# RF-BPF.net
KiCad netlist of a schematic drawn in Altium Designer
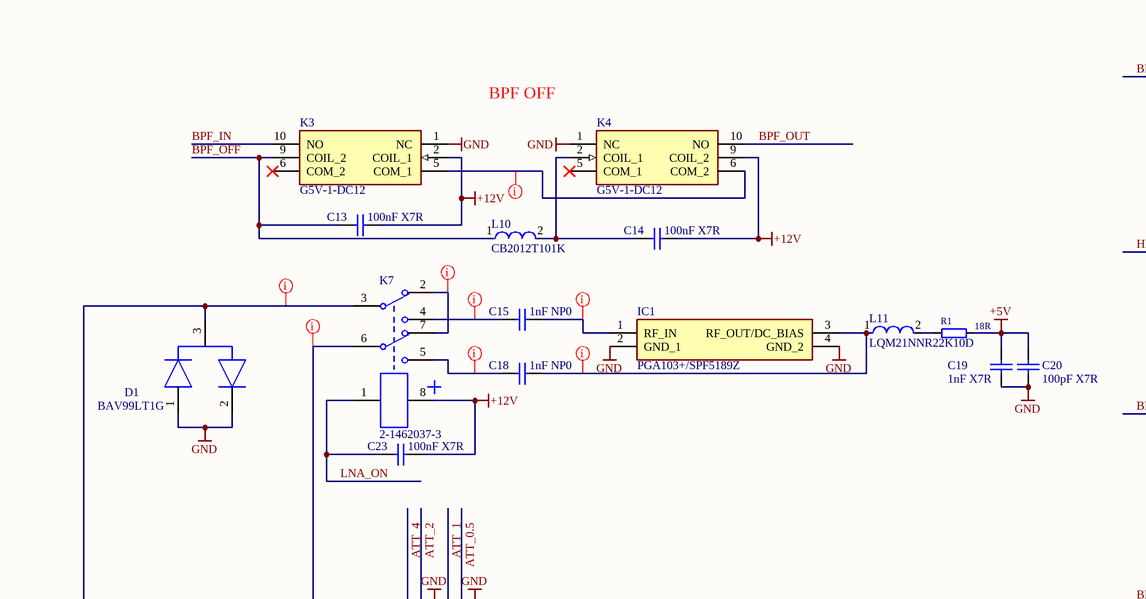
[diagram p0: RF-BPF.SchDoc, top left]
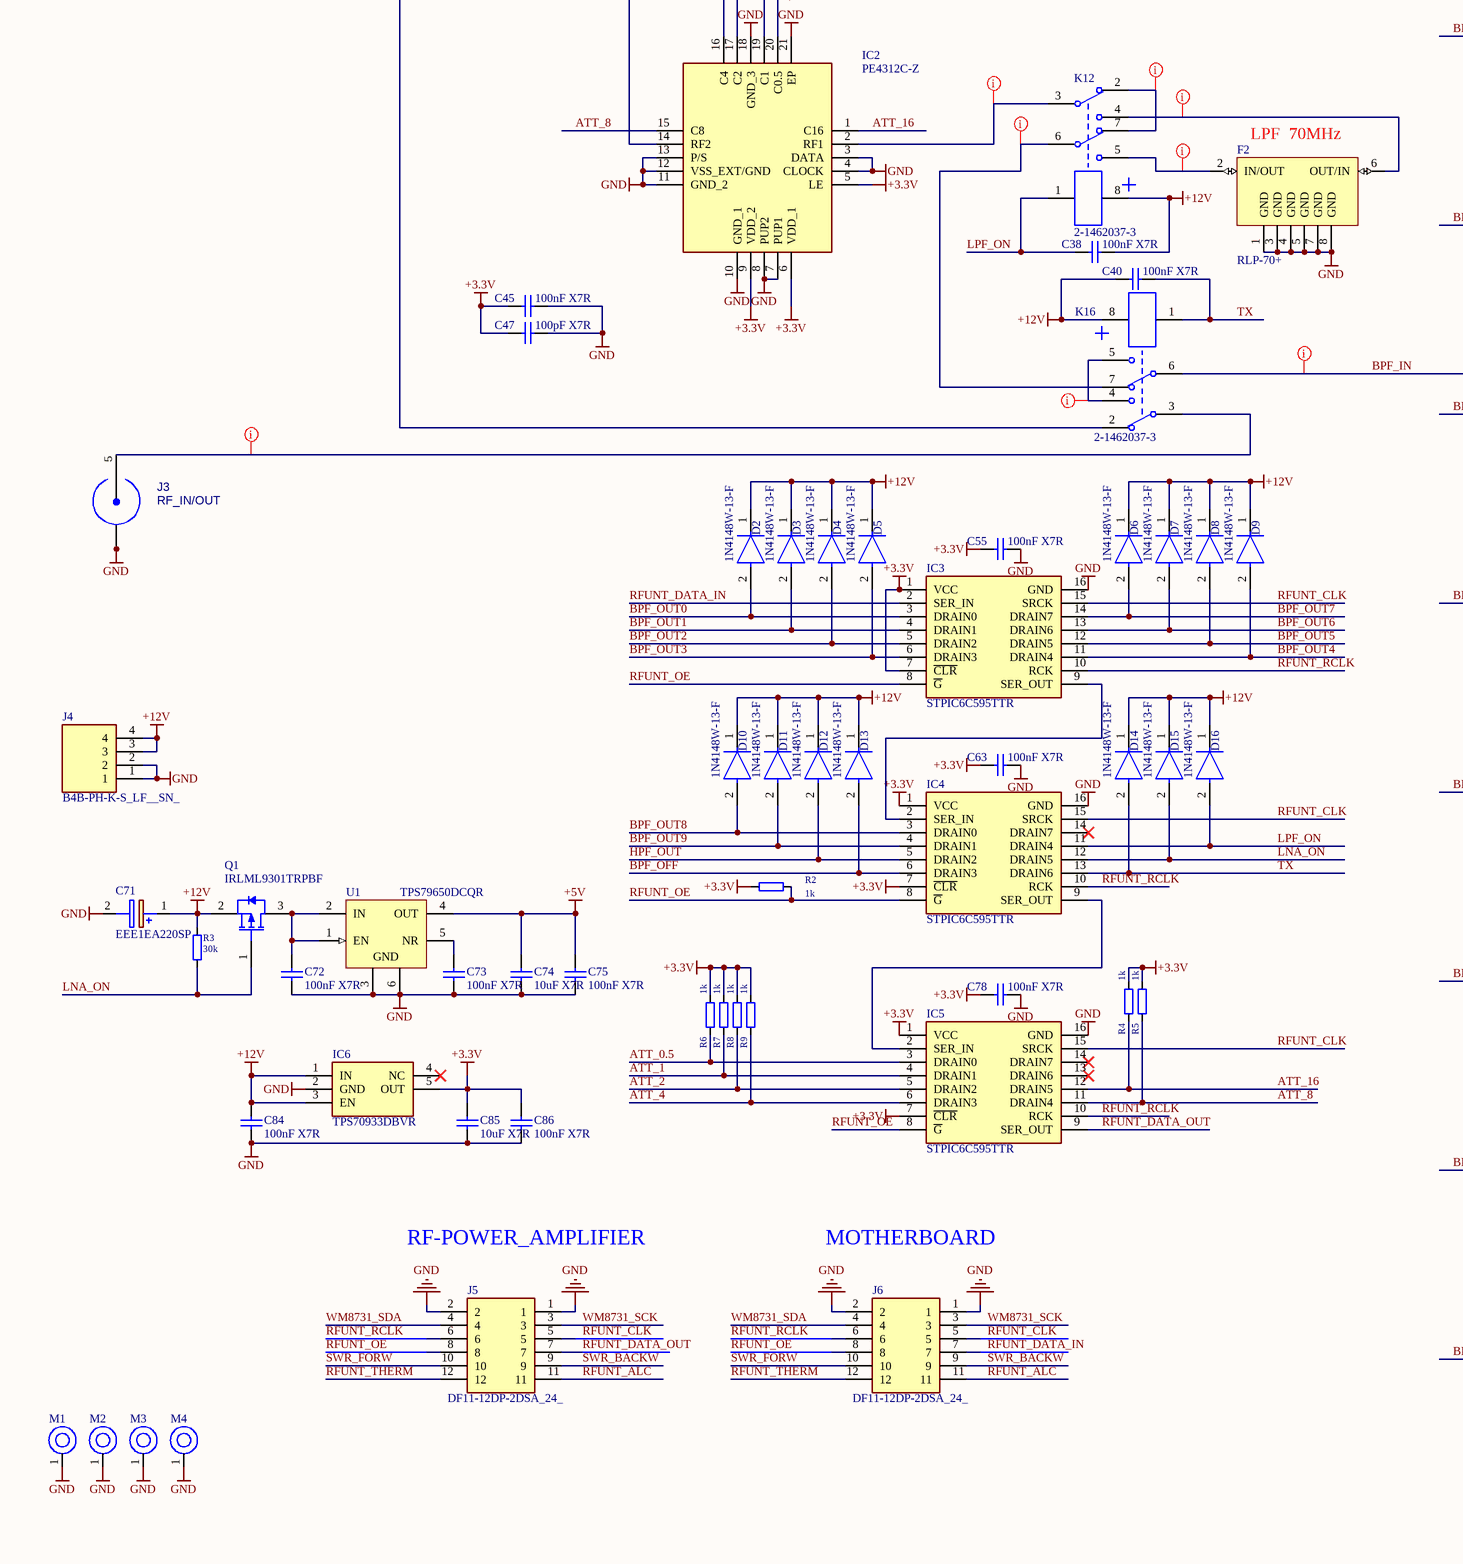
[diagram p1: RF-BPF.SchDoc, bottom left]
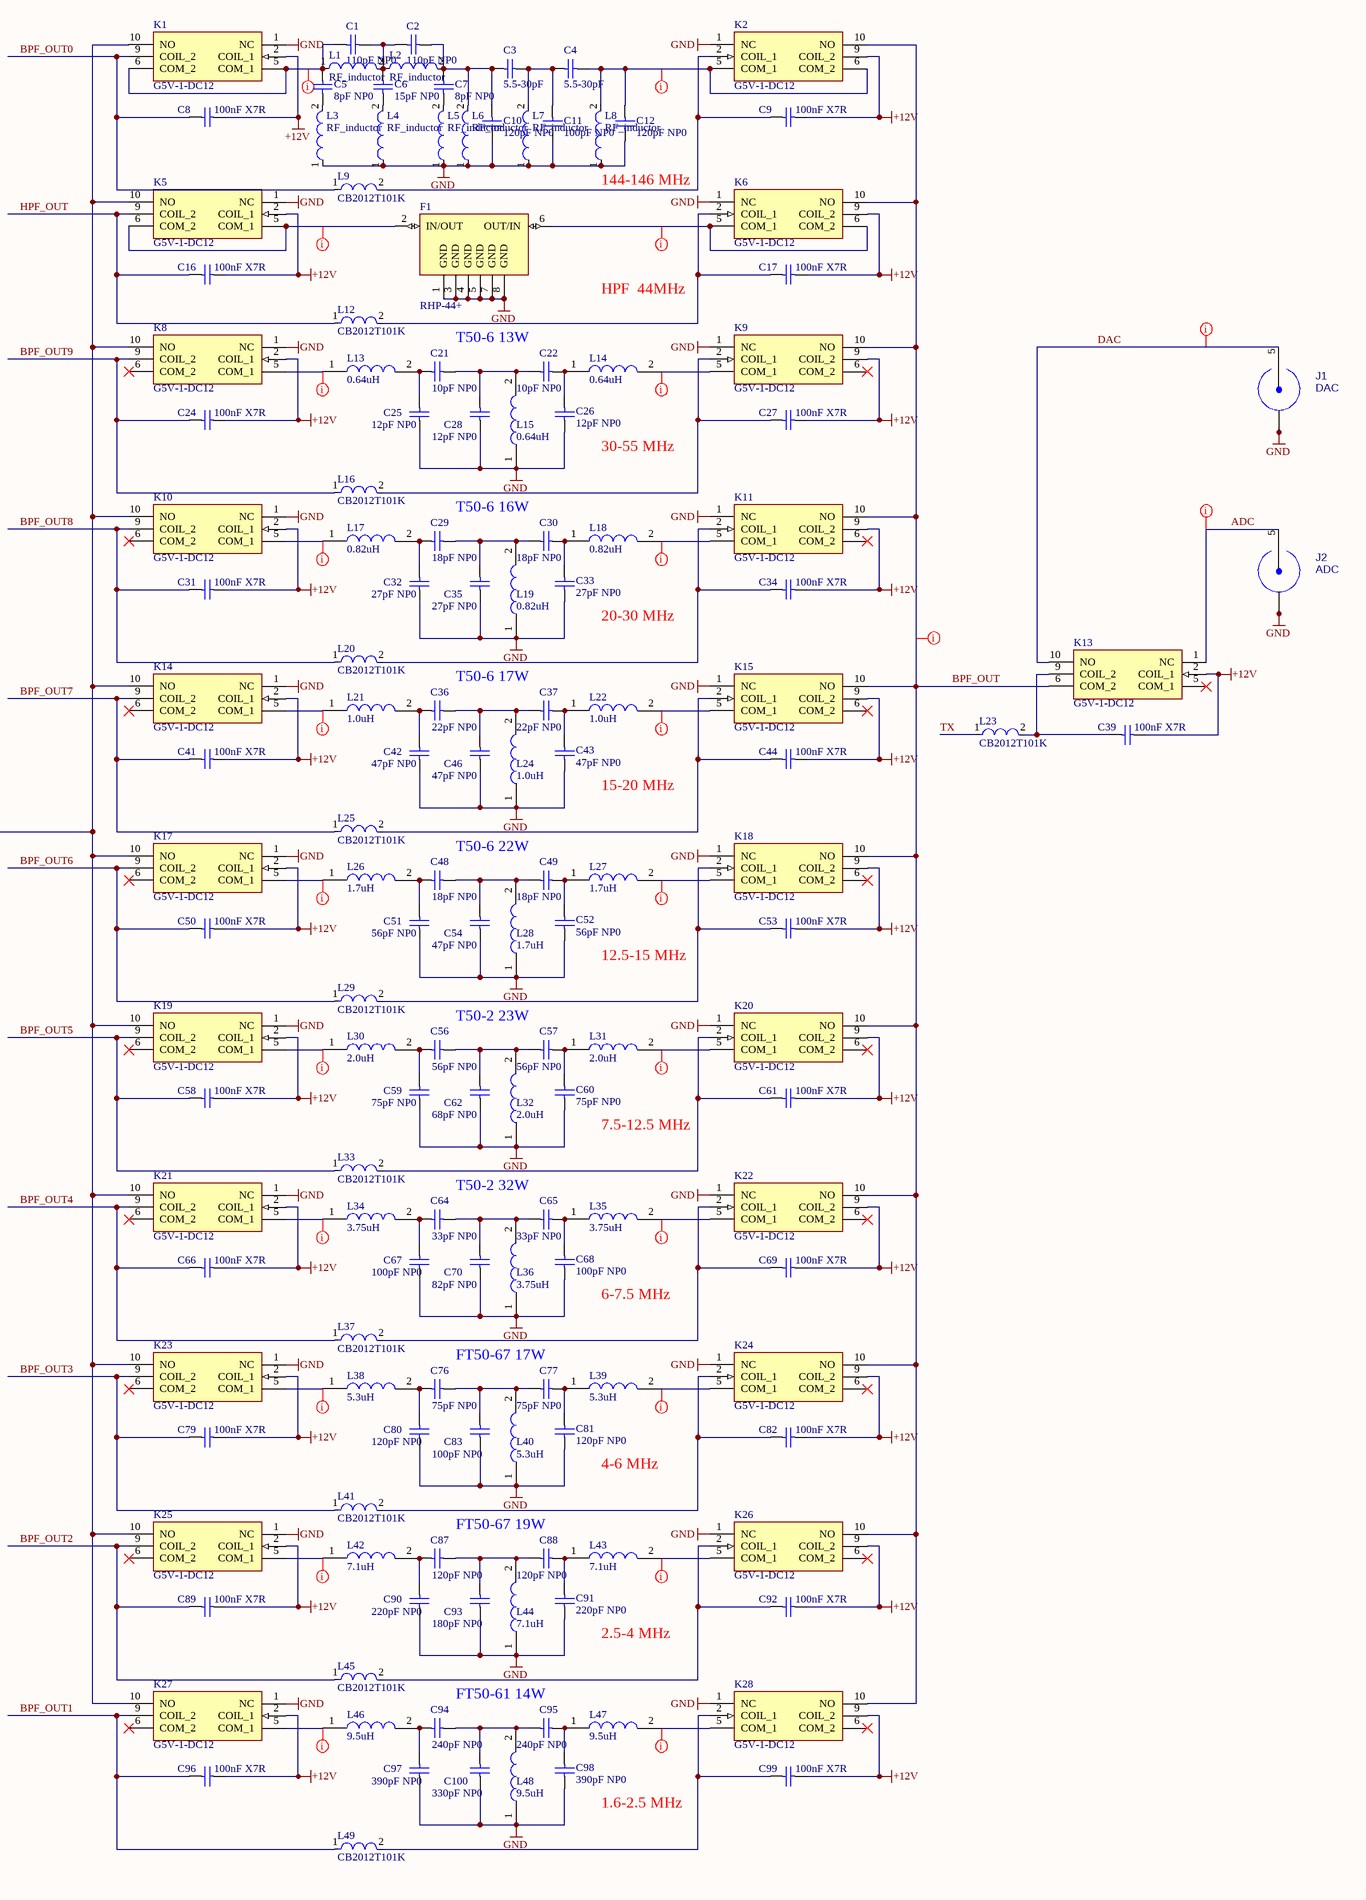
[diagram p2: RF-BPF.SchDoc, bottom right]

(export (version "E")
  (design (tool "Eeschema 10.0.6"))
  (components
    (comp (ref "C1")
      (value "110pF NP0")
      (footprint "C-0805")
      (description "Ceramic Multilayer Capacitor")
      (fields (field (name "MANUFACTURER") "Yageo/Phycomp") (field (name "TOLERANCE") "±10%"))
      (libsource (lib "Hristo") (part "C semi"))
    )
    (comp (ref "C2")
      (value "110pF NP0")
      (footprint "C-0805")
      (description "Ceramic Multilayer Capacitor")
      (fields (field (name "MANUFACTURER") "Yageo/Phycomp") (field (name "TOLERANCE") "±10%"))
      (libsource (lib "Hristo") (part "C semi"))
    )
    (comp (ref "C3")
      (value "5.5-30pF")
      (footprint "CAP-ADJ-SMD_L4.5-W3.2-L")
      (description "Ceramic Multilayer Capacitor")
      (fields (field (name "MANUFACTURER") "Yageo/Phycomp") (field (name "TOLERANCE") "±10%"))
      (libsource (lib "Hristo") (part "C semi"))
    )
    (comp (ref "C4")
      (value "5.5-30pF")
      (footprint "CAP-ADJ-SMD_L4.5-W3.2-L")
      (description "Ceramic Multilayer Capacitor")
      (fields (field (name "MANUFACTURER") "Yageo/Phycomp") (field (name "TOLERANCE") "±10%"))
      (libsource (lib "Hristo") (part "C semi"))
    )
    (comp (ref "C5")
      (value "8pF NP0")
      (footprint "C-0805")
      (description "Ceramic Multilayer Capacitor")
      (fields (field (name "MANUFACTURER") "Yageo/Phycomp") (field (name "TOLERANCE") "±10%"))
      (libsource (lib "Hristo") (part "C semi"))
    )
    (comp (ref "C6")
      (value "15pF NP0")
      (footprint "C-0805")
      (description "Ceramic Multilayer Capacitor")
      (fields (field (name "MANUFACTURER") "Yageo/Phycomp") (field (name "TOLERANCE") "±10%"))
      (libsource (lib "Hristo") (part "C semi"))
    )
    (comp (ref "C7")
      (value "8pF NP0")
      (footprint "C-0805")
      (description "Ceramic Multilayer Capacitor")
      (fields (field (name "MANUFACTURER") "Yageo/Phycomp") (field (name "TOLERANCE") "±10%"))
      (libsource (lib "Hristo") (part "C semi"))
    )
    (comp (ref "C8")
      (value "100nF X7R")
      (footprint "C-0805")
      (description "Ceramic Multilayer Capacitor")
      (fields (field (name "MANUFACTURER") "Yageo/Phycomp") (field (name "TOLERANCE") "±10%"))
      (libsource (lib "Hristo") (part "C semi"))
    )
    (comp (ref "C9")
      (value "100nF X7R")
      (footprint "C-0805")
      (description "Ceramic Multilayer Capacitor")
      (fields (field (name "MANUFACTURER") "Yageo/Phycomp") (field (name "TOLERANCE") "±10%"))
      (libsource (lib "Hristo") (part "C semi"))
    )
    (comp (ref "C10")
      (value "120pF NP0")
      (footprint "C-0805")
      (description "Ceramic Multilayer Capacitor")
      (fields (field (name "MANUFACTURER") "Yageo/Phycomp") (field (name "TOLERANCE") "±10%"))
      (libsource (lib "Hristo") (part "C semi"))
    )
    (comp (ref "C11")
      (value "100pF NP0")
      (footprint "C-0805")
      (description "Ceramic Multilayer Capacitor")
      (fields (field (name "MANUFACTURER") "Yageo/Phycomp") (field (name "TOLERANCE") "±10%"))
      (libsource (lib "Hristo") (part "C semi"))
    )
    (comp (ref "C12")
      (value "120pF NP0")
      (footprint "C-0805")
      (description "Ceramic Multilayer Capacitor")
      (fields (field (name "MANUFACTURER") "Yageo/Phycomp") (field (name "TOLERANCE") "±10%"))
      (libsource (lib "Hristo") (part "C semi"))
    )
    (comp (ref "C13")
      (value "100nF X7R")
      (footprint "C-0805")
      (description "Ceramic Multilayer Capacitor")
      (fields (field (name "MANUFACTURER") "Yageo/Phycomp") (field (name "TOLERANCE") "±10%"))
      (libsource (lib "Hristo") (part "C semi"))
    )
    (comp (ref "C14")
      (value "100nF X7R")
      (footprint "C-0805")
      (description "Ceramic Multilayer Capacitor")
      (fields (field (name "MANUFACTURER") "Yageo/Phycomp") (field (name "TOLERANCE") "±10%"))
      (libsource (lib "Hristo") (part "C semi"))
    )
    (comp (ref "C15")
      (value "1nF NP0")
      (footprint "C-0805")
      (description "Ceramic Multilayer Capacitor")
      (fields (field (name "MANUFACTURER") "Yageo/Phycomp") (field (name "TOLERANCE") "±10%"))
      (libsource (lib "Hristo") (part "C semi"))
    )
    (comp (ref "C16")
      (value "100nF X7R")
      (footprint "C-0805")
      (description "Ceramic Multilayer Capacitor")
      (fields (field (name "MANUFACTURER") "Yageo/Phycomp") (field (name "TOLERANCE") "±10%"))
      (libsource (lib "Hristo") (part "C semi"))
    )
    (comp (ref "C17")
      (value "100nF X7R")
      (footprint "C-0805")
      (description "Ceramic Multilayer Capacitor")
      (fields (field (name "MANUFACTURER") "Yageo/Phycomp") (field (name "TOLERANCE") "±10%"))
      (libsource (lib "Hristo") (part "C semi"))
    )
    (comp (ref "C18")
      (value "1nF NP0")
      (footprint "C-0805")
      (description "Ceramic Multilayer Capacitor")
      (fields (field (name "MANUFACTURER") "Yageo/Phycomp") (field (name "TOLERANCE") "±10%"))
      (libsource (lib "Hristo") (part "C semi"))
    )
    (comp (ref "C19")
      (value "1nF X7R")
      (footprint "C-0603")
      (description "Ceramic Multilayer Capacitor")
      (fields (field (name "MANUFACTURER") "Yageo/Phycomp") (field (name "TOLERANCE") "±10%"))
      (libsource (lib "Hristo") (part "C semi"))
    )
    (comp (ref "C20")
      (value "100pF X7R")
      (footprint "C-0603")
      (description "Ceramic Multilayer Capacitor")
      (fields (field (name "MANUFACTURER") "Yageo/Phycomp") (field (name "TOLERANCE") "±10%"))
      (libsource (lib "Hristo") (part "C semi"))
    )
    (comp (ref "C21")
      (value "10pF NP0")
      (footprint "C-0805")
      (description "Ceramic Multilayer Capacitor")
      (fields (field (name "MANUFACTURER") "Yageo/Phycomp") (field (name "TOLERANCE") "±10%"))
      (libsource (lib "Hristo") (part "C semi"))
    )
    (comp (ref "C22")
      (value "10pF NP0")
      (footprint "C-0805")
      (description "Ceramic Multilayer Capacitor")
      (fields (field (name "MANUFACTURER") "Yageo/Phycomp") (field (name "TOLERANCE") "±10%"))
      (libsource (lib "Hristo") (part "C semi"))
    )
    (comp (ref "C23")
      (value "100nF X7R")
      (footprint "C-0805")
      (description "Ceramic Multilayer Capacitor")
      (fields (field (name "MANUFACTURER") "Yageo/Phycomp") (field (name "TOLERANCE") "±10%"))
      (libsource (lib "Hristo") (part "C semi"))
    )
    (comp (ref "C24")
      (value "100nF X7R")
      (footprint "C-0805")
      (description "Ceramic Multilayer Capacitor")
      (fields (field (name "MANUFACTURER") "Yageo/Phycomp") (field (name "TOLERANCE") "±10%"))
      (libsource (lib "Hristo") (part "C semi"))
    )
    (comp (ref "C25")
      (value "12pF NP0")
      (footprint "C-0805")
      (description "Ceramic Multilayer Capacitor")
      (fields (field (name "MANUFACTURER") "Yageo/Phycomp") (field (name "TOLERANCE") "±10%"))
      (libsource (lib "Hristo") (part "C semi"))
    )
    (comp (ref "C26")
      (value "12pF NP0")
      (footprint "C-0805")
      (description "Ceramic Multilayer Capacitor")
      (fields (field (name "MANUFACTURER") "Yageo/Phycomp") (field (name "TOLERANCE") "±10%"))
      (libsource (lib "Hristo") (part "C semi"))
    )
    (comp (ref "C27")
      (value "100nF X7R")
      (footprint "C-0805")
      (description "Ceramic Multilayer Capacitor")
      (fields (field (name "MANUFACTURER") "Yageo/Phycomp") (field (name "TOLERANCE") "±10%"))
      (libsource (lib "Hristo") (part "C semi"))
    )
    (comp (ref "C28")
      (value "12pF NP0")
      (footprint "C-0805")
      (description "Ceramic Multilayer Capacitor")
      (fields (field (name "MANUFACTURER") "Yageo/Phycomp") (field (name "TOLERANCE") "±10%"))
      (libsource (lib "Hristo") (part "C semi"))
    )
    (comp (ref "C29")
      (value "18pF NP0")
      (footprint "C-0805")
      (description "Ceramic Multilayer Capacitor")
      (fields (field (name "MANUFACTURER") "Yageo/Phycomp") (field (name "TOLERANCE") "±10%"))
      (libsource (lib "Hristo") (part "C semi"))
    )
    (comp (ref "C30")
      (value "18pF NP0")
      (footprint "C-0805")
      (description "Ceramic Multilayer Capacitor")
      (fields (field (name "MANUFACTURER") "Yageo/Phycomp") (field (name "TOLERANCE") "±10%"))
      (libsource (lib "Hristo") (part "C semi"))
    )
    (comp (ref "C31")
      (value "100nF X7R")
      (footprint "C-0805")
      (description "Ceramic Multilayer Capacitor")
      (fields (field (name "MANUFACTURER") "Yageo/Phycomp") (field (name "TOLERANCE") "±10%"))
      (libsource (lib "Hristo") (part "C semi"))
    )
    (comp (ref "C32")
      (value "27pF NP0")
      (footprint "C-0805")
      (description "Ceramic Multilayer Capacitor")
      (fields (field (name "MANUFACTURER") "Yageo/Phycomp") (field (name "TOLERANCE") "±10%"))
      (libsource (lib "Hristo") (part "C semi"))
    )
    (comp (ref "C33")
      (value "27pF NP0")
      (footprint "C-0805")
      (description "Ceramic Multilayer Capacitor")
      (fields (field (name "MANUFACTURER") "Yageo/Phycomp") (field (name "TOLERANCE") "±10%"))
      (libsource (lib "Hristo") (part "C semi"))
    )
    (comp (ref "C34")
      (value "100nF X7R")
      (footprint "C-0805")
      (description "Ceramic Multilayer Capacitor")
      (fields (field (name "MANUFACTURER") "Yageo/Phycomp") (field (name "TOLERANCE") "±10%"))
      (libsource (lib "Hristo") (part "C semi"))
    )
    (comp (ref "C35")
      (value "27pF NP0")
      (footprint "C-0805")
      (description "Ceramic Multilayer Capacitor")
      (fields (field (name "MANUFACTURER") "Yageo/Phycomp") (field (name "TOLERANCE") "±10%"))
      (libsource (lib "Hristo") (part "C semi"))
    )
    (comp (ref "C36")
      (value "22pF NP0")
      (footprint "C-0805")
      (description "Ceramic Multilayer Capacitor")
      (fields (field (name "MANUFACTURER") "Yageo/Phycomp") (field (name "TOLERANCE") "±10%"))
      (libsource (lib "Hristo") (part "C semi"))
    )
    (comp (ref "C37")
      (value "22pF NP0")
      (footprint "C-0805")
      (description "Ceramic Multilayer Capacitor")
      (fields (field (name "MANUFACTURER") "Yageo/Phycomp") (field (name "TOLERANCE") "±10%"))
      (libsource (lib "Hristo") (part "C semi"))
    )
    (comp (ref "C38")
      (value "100nF X7R")
      (footprint "C-0805")
      (description "Ceramic Multilayer Capacitor")
      (fields (field (name "MANUFACTURER") "Yageo/Phycomp") (field (name "TOLERANCE") "±10%"))
      (libsource (lib "Hristo") (part "C semi"))
    )
    (comp (ref "C39")
      (value "100nF X7R")
      (footprint "C-0805")
      (description "Ceramic Multilayer Capacitor")
      (fields (field (name "MANUFACTURER") "Yageo/Phycomp") (field (name "TOLERANCE") "±10%"))
      (libsource (lib "Hristo") (part "C semi"))
    )
    (comp (ref "C40")
      (value "100nF X7R")
      (footprint "C-0805")
      (description "Ceramic Multilayer Capacitor")
      (fields (field (name "MANUFACTURER") "Yageo/Phycomp") (field (name "TOLERANCE") "±10%"))
      (libsource (lib "Hristo") (part "C semi"))
    )
    (comp (ref "C41")
      (value "100nF X7R")
      (footprint "C-0805")
      (description "Ceramic Multilayer Capacitor")
      (fields (field (name "MANUFACTURER") "Yageo/Phycomp") (field (name "TOLERANCE") "±10%"))
      (libsource (lib "Hristo") (part "C semi"))
    )
    (comp (ref "C42")
      (value "47pF NP0")
      (footprint "C-0805")
      (description "Ceramic Multilayer Capacitor")
      (fields (field (name "MANUFACTURER") "Yageo/Phycomp") (field (name "TOLERANCE") "±10%"))
      (libsource (lib "Hristo") (part "C semi"))
    )
    (comp (ref "C43")
      (value "47pF NP0")
      (footprint "C-0805")
      (description "Ceramic Multilayer Capacitor")
      (fields (field (name "MANUFACTURER") "Yageo/Phycomp") (field (name "TOLERANCE") "±10%"))
      (libsource (lib "Hristo") (part "C semi"))
    )
    (comp (ref "C44")
      (value "100nF X7R")
      (footprint "C-0805")
      (description "Ceramic Multilayer Capacitor")
      (fields (field (name "MANUFACTURER") "Yageo/Phycomp") (field (name "TOLERANCE") "±10%"))
      (libsource (lib "Hristo") (part "C semi"))
    )
    (comp (ref "C45")
      (value "100nF X7R")
      (footprint "C-0603")
      (description "Ceramic Multilayer Capacitor")
      (fields (field (name "MANUFACTURER") "Yageo/Phycomp") (field (name "TOLERANCE") "±10%"))
      (libsource (lib "Hristo") (part "C semi"))
    )
    (comp (ref "C46")
      (value "47pF NP0")
      (footprint "C-0805")
      (description "Ceramic Multilayer Capacitor")
      (fields (field (name "MANUFACTURER") "Yageo/Phycomp") (field (name "TOLERANCE") "±10%"))
      (libsource (lib "Hristo") (part "C semi"))
    )
    (comp (ref "C47")
      (value "100pF X7R")
      (footprint "C-0603")
      (description "Ceramic Multilayer Capacitor")
      (fields (field (name "MANUFACTURER") "Yageo/Phycomp") (field (name "TOLERANCE") "±10%"))
      (libsource (lib "Hristo") (part "C semi"))
    )
    (comp (ref "C48")
      (value "18pF NP0")
      (footprint "C-0805")
      (description "Ceramic Multilayer Capacitor")
      (fields (field (name "MANUFACTURER") "Yageo/Phycomp") (field (name "TOLERANCE") "±10%"))
      (libsource (lib "Hristo") (part "C semi"))
    )
    (comp (ref "C49")
      (value "18pF NP0")
      (footprint "C-0805")
      (description "Ceramic Multilayer Capacitor")
      (fields (field (name "MANUFACTURER") "Yageo/Phycomp") (field (name "TOLERANCE") "±10%"))
      (libsource (lib "Hristo") (part "C semi"))
    )
    (comp (ref "C50")
      (value "100nF X7R")
      (footprint "C-0805")
      (description "Ceramic Multilayer Capacitor")
      (fields (field (name "MANUFACTURER") "Yageo/Phycomp") (field (name "TOLERANCE") "±10%"))
      (libsource (lib "Hristo") (part "C semi"))
    )
    (comp (ref "C51")
      (value "56pF NP0")
      (footprint "C-0805")
      (description "Ceramic Multilayer Capacitor")
      (fields (field (name "MANUFACTURER") "Yageo/Phycomp") (field (name "TOLERANCE") "±10%"))
      (libsource (lib "Hristo") (part "C semi"))
    )
    (comp (ref "C52")
      (value "56pF NP0")
      (footprint "C-0805")
      (description "Ceramic Multilayer Capacitor")
      (fields (field (name "MANUFACTURER") "Yageo/Phycomp") (field (name "TOLERANCE") "±10%"))
      (libsource (lib "Hristo") (part "C semi"))
    )
    (comp (ref "C53")
      (value "100nF X7R")
      (footprint "C-0805")
      (description "Ceramic Multilayer Capacitor")
      (fields (field (name "MANUFACTURER") "Yageo/Phycomp") (field (name "TOLERANCE") "±10%"))
      (libsource (lib "Hristo") (part "C semi"))
    )
    (comp (ref "C54")
      (value "47pF NP0")
      (footprint "C-0805")
      (description "Ceramic Multilayer Capacitor")
      (fields (field (name "MANUFACTURER") "Yageo/Phycomp") (field (name "TOLERANCE") "±10%"))
      (libsource (lib "Hristo") (part "C semi"))
    )
    (comp (ref "C55")
      (value "100nF X7R")
      (footprint "C-0603")
      (description "Ceramic Multilayer Capacitor")
      (fields (field (name "MANUFACTURER") "Yageo/Phycomp") (field (name "TOLERANCE") "±10%"))
      (libsource (lib "Hristo") (part "C semi"))
    )
    (comp (ref "C56")
      (value "56pF NP0")
      (footprint "C-0805")
      (description "Ceramic Multilayer Capacitor")
      (fields (field (name "MANUFACTURER") "Yageo/Phycomp") (field (name "TOLERANCE") "±10%"))
      (libsource (lib "Hristo") (part "C semi"))
    )
    (comp (ref "C57")
      (value "56pF NP0")
      (footprint "C-0805")
      (description "Ceramic Multilayer Capacitor")
      (fields (field (name "MANUFACTURER") "Yageo/Phycomp") (field (name "TOLERANCE") "±10%"))
      (libsource (lib "Hristo") (part "C semi"))
    )
    (comp (ref "C58")
      (value "100nF X7R")
      (footprint "C-0805")
      (description "Ceramic Multilayer Capacitor")
      (fields (field (name "MANUFACTURER") "Yageo/Phycomp") (field (name "TOLERANCE") "±10%"))
      (libsource (lib "Hristo") (part "C semi"))
    )
    (comp (ref "C59")
      (value "75pF NP0")
      (footprint "C-0805")
      (description "Ceramic Multilayer Capacitor")
      (fields (field (name "MANUFACTURER") "Yageo/Phycomp") (field (name "TOLERANCE") "±10%"))
      (libsource (lib "Hristo") (part "C semi"))
    )
    (comp (ref "C60")
      (value "75pF NP0")
      (footprint "C-0805")
      (description "Ceramic Multilayer Capacitor")
      (fields (field (name "MANUFACTURER") "Yageo/Phycomp") (field (name "TOLERANCE") "±10%"))
      (libsource (lib "Hristo") (part "C semi"))
    )
    (comp (ref "C61")
      (value "100nF X7R")
      (footprint "C-0805")
      (description "Ceramic Multilayer Capacitor")
      (fields (field (name "MANUFACTURER") "Yageo/Phycomp") (field (name "TOLERANCE") "±10%"))
      (libsource (lib "Hristo") (part "C semi"))
    )
    (comp (ref "C62")
      (value "68pF NP0")
      (footprint "C-0805")
      (description "Ceramic Multilayer Capacitor")
      (fields (field (name "MANUFACTURER") "Yageo/Phycomp") (field (name "TOLERANCE") "±10%"))
      (libsource (lib "Hristo") (part "C semi"))
    )
    (comp (ref "C63")
      (value "100nF X7R")
      (footprint "C-0603")
      (description "Ceramic Multilayer Capacitor")
      (fields (field (name "MANUFACTURER") "Yageo/Phycomp") (field (name "TOLERANCE") "±10%"))
      (libsource (lib "Hristo") (part "C semi"))
    )
    (comp (ref "C64")
      (value "33pF NP0")
      (footprint "C-0805")
      (description "Ceramic Multilayer Capacitor")
      (fields (field (name "MANUFACTURER") "Yageo/Phycomp") (field (name "TOLERANCE") "±10%"))
      (libsource (lib "Hristo") (part "C semi"))
    )
    (comp (ref "C65")
      (value "33pF NP0")
      (footprint "C-0805")
      (description "Ceramic Multilayer Capacitor")
      (fields (field (name "MANUFACTURER") "Yageo/Phycomp") (field (name "TOLERANCE") "±10%"))
      (libsource (lib "Hristo") (part "C semi"))
    )
    (comp (ref "C66")
      (value "100nF X7R")
      (footprint "C-0805")
      (description "Ceramic Multilayer Capacitor")
      (fields (field (name "MANUFACTURER") "Yageo/Phycomp") (field (name "TOLERANCE") "±10%"))
      (libsource (lib "Hristo") (part "C semi"))
    )
    (comp (ref "C67")
      (value "100pF NP0")
      (footprint "C-0805")
      (description "Ceramic Multilayer Capacitor")
      (fields (field (name "MANUFACTURER") "Yageo/Phycomp") (field (name "TOLERANCE") "±10%"))
      (libsource (lib "Hristo") (part "C semi"))
    )
    (comp (ref "C68")
      (value "100pF NP0")
      (footprint "C-0805")
      (description "Ceramic Multilayer Capacitor")
      (fields (field (name "MANUFACTURER") "Yageo/Phycomp") (field (name "TOLERANCE") "±10%"))
      (libsource (lib "Hristo") (part "C semi"))
    )
    (comp (ref "C69")
      (value "100nF X7R")
      (footprint "C-0805")
      (description "Ceramic Multilayer Capacitor")
      (fields (field (name "MANUFACTURER") "Yageo/Phycomp") (field (name "TOLERANCE") "±10%"))
      (libsource (lib "Hristo") (part "C semi"))
    )
    (comp (ref "C70")
      (value "82pF NP0")
      (footprint "C-0805")
      (description "Ceramic Multilayer Capacitor")
      (fields (field (name "MANUFACTURER") "Yageo/Phycomp") (field (name "TOLERANCE") "±10%"))
      (libsource (lib "Hristo") (part "C semi"))
    )
    (comp (ref "C71")
      (value "EEE1EA220SP")
      (footprint "SamacSys:EEE1AA101SP")
      (description "Capacitor Polarised")
      (libsource (lib "SamacSys") (part "EEE1EA220SP"))
    )
    (comp (ref "C72")
      (value "100nF X7R")
      (footprint "C-0603")
      (description "Ceramic Multilayer Capacitor")
      (fields (field (name "MANUFACTURER") "Yageo/Phycomp") (field (name "TOLERANCE") "±10%"))
      (libsource (lib "Hristo") (part "C semi"))
    )
    (comp (ref "C73")
      (value "100nF X7R")
      (footprint "C-0603")
      (description "Ceramic Multilayer Capacitor")
      (fields (field (name "MANUFACTURER") "Yageo/Phycomp") (field (name "TOLERANCE") "±10%"))
      (libsource (lib "Hristo") (part "C semi"))
    )
    (comp (ref "C74")
      (value "10uF X7R")
      (footprint "C-0603")
      (description "Ceramic Multilayer Capacitor")
      (fields (field (name "MANUFACTURER") "Yageo/Phycomp") (field (name "TOLERANCE") "±10%"))
      (libsource (lib "Hristo") (part "C semi"))
    )
    (comp (ref "C75")
      (value "100nF X7R")
      (footprint "C-0603")
      (description "Ceramic Multilayer Capacitor")
      (fields (field (name "MANUFACTURER") "Yageo/Phycomp") (field (name "TOLERANCE") "±10%"))
      (libsource (lib "Hristo") (part "C semi"))
    )
    (comp (ref "C76")
      (value "75pF NP0")
      (footprint "C-0805")
      (description "Ceramic Multilayer Capacitor")
      (fields (field (name "MANUFACTURER") "Yageo/Phycomp") (field (name "TOLERANCE") "±10%"))
      (libsource (lib "Hristo") (part "C semi"))
    )
    (comp (ref "C77")
      (value "75pF NP0")
      (footprint "C-0805")
      (description "Ceramic Multilayer Capacitor")
      (fields (field (name "MANUFACTURER") "Yageo/Phycomp") (field (name "TOLERANCE") "±10%"))
      (libsource (lib "Hristo") (part "C semi"))
    )
    (comp (ref "C78")
      (value "100nF X7R")
      (footprint "C-0603")
      (description "Ceramic Multilayer Capacitor")
      (fields (field (name "MANUFACTURER") "Yageo/Phycomp") (field (name "TOLERANCE") "±10%"))
      (libsource (lib "Hristo") (part "C semi"))
    )
    (comp (ref "C79")
      (value "100nF X7R")
      (footprint "C-0805")
      (description "Ceramic Multilayer Capacitor")
      (fields (field (name "MANUFACTURER") "Yageo/Phycomp") (field (name "TOLERANCE") "±10%"))
      (libsource (lib "Hristo") (part "C semi"))
    )
    (comp (ref "C80")
      (value "120pF NP0")
      (footprint "C-0805")
      (description "Ceramic Multilayer Capacitor")
      (fields (field (name "MANUFACTURER") "Yageo/Phycomp") (field (name "TOLERANCE") "±10%"))
      (libsource (lib "Hristo") (part "C semi"))
    )
    (comp (ref "C81")
      (value "120pF NP0")
      (footprint "C-0805")
      (description "Ceramic Multilayer Capacitor")
      (fields (field (name "MANUFACTURER") "Yageo/Phycomp") (field (name "TOLERANCE") "±10%"))
      (libsource (lib "Hristo") (part "C semi"))
    )
    (comp (ref "C82")
      (value "100nF X7R")
      (footprint "C-0805")
      (description "Ceramic Multilayer Capacitor")
      (fields (field (name "MANUFACTURER") "Yageo/Phycomp") (field (name "TOLERANCE") "±10%"))
      (libsource (lib "Hristo") (part "C semi"))
    )
    (comp (ref "C83")
      (value "100pF NP0")
      (footprint "C-0805")
      (description "Ceramic Multilayer Capacitor")
      (fields (field (name "MANUFACTURER") "Yageo/Phycomp") (field (name "TOLERANCE") "±10%"))
      (libsource (lib "Hristo") (part "C semi"))
    )
    (comp (ref "C84")
      (value "100nF X7R")
      (footprint "C-0603")
      (description "Ceramic Multilayer Capacitor")
      (fields (field (name "MANUFACTURER") "Yageo/Phycomp") (field (name "TOLERANCE") "±10%"))
      (libsource (lib "Hristo") (part "C semi"))
    )
    (comp (ref "C85")
      (value "10uF X7R")
      (footprint "C-0603")
      (description "Ceramic Multilayer Capacitor")
      (fields (field (name "MANUFACTURER") "Yageo/Phycomp") (field (name "TOLERANCE") "±10%"))
      (libsource (lib "Hristo") (part "C semi"))
    )
    (comp (ref "C86")
      (value "100nF X7R")
      (footprint "C-0603")
      (description "Ceramic Multilayer Capacitor")
      (fields (field (name "MANUFACTURER") "Yageo/Phycomp") (field (name "TOLERANCE") "±10%"))
      (libsource (lib "Hristo") (part "C semi"))
    )
    (comp (ref "C87")
      (value "120pF NP0")
      (footprint "C-0805")
      (description "Ceramic Multilayer Capacitor")
      (fields (field (name "MANUFACTURER") "Yageo/Phycomp") (field (name "TOLERANCE") "±10%"))
      (libsource (lib "Hristo") (part "C semi"))
    )
    (comp (ref "C88")
      (value "120pF NP0")
      (footprint "C-0805")
      (description "Ceramic Multilayer Capacitor")
      (fields (field (name "MANUFACTURER") "Yageo/Phycomp") (field (name "TOLERANCE") "±10%"))
      (libsource (lib "Hristo") (part "C semi"))
    )
    (comp (ref "C89")
      (value "100nF X7R")
      (footprint "C-0805")
      (description "Ceramic Multilayer Capacitor")
      (fields (field (name "MANUFACTURER") "Yageo/Phycomp") (field (name "TOLERANCE") "±10%"))
      (libsource (lib "Hristo") (part "C semi"))
    )
    (comp (ref "C90")
      (value "220pF NP0")
      (footprint "C-0805")
      (description "Ceramic Multilayer Capacitor")
      (fields (field (name "MANUFACTURER") "Yageo/Phycomp") (field (name "TOLERANCE") "±10%"))
      (libsource (lib "Hristo") (part "C semi"))
    )
    (comp (ref "C91")
      (value "220pF NP0")
      (footprint "C-0805")
      (description "Ceramic Multilayer Capacitor")
      (fields (field (name "MANUFACTURER") "Yageo/Phycomp") (field (name "TOLERANCE") "±10%"))
      (libsource (lib "Hristo") (part "C semi"))
    )
    (comp (ref "C92")
      (value "100nF X7R")
      (footprint "C-0805")
      (description "Ceramic Multilayer Capacitor")
      (fields (field (name "MANUFACTURER") "Yageo/Phycomp") (field (name "TOLERANCE") "±10%"))
      (libsource (lib "Hristo") (part "C semi"))
    )
    (comp (ref "C93")
      (value "180pF NP0")
      (footprint "C-0805")
      (description "Ceramic Multilayer Capacitor")
      (fields (field (name "MANUFACTURER") "Yageo/Phycomp") (field (name "TOLERANCE") "±10%"))
      (libsource (lib "Hristo") (part "C semi"))
    )
    (comp (ref "C94")
      (value "240pF NP0")
      (footprint "C-0805")
      (description "Ceramic Multilayer Capacitor")
      (fields (field (name "MANUFACTURER") "Yageo/Phycomp") (field (name "TOLERANCE") "±10%"))
      (libsource (lib "Hristo") (part "C semi"))
    )
    (comp (ref "C95")
      (value "240pF NP0")
      (footprint "C-0805")
      (description "Ceramic Multilayer Capacitor")
      (fields (field (name "MANUFACTURER") "Yageo/Phycomp") (field (name "TOLERANCE") "±10%"))
      (libsource (lib "Hristo") (part "C semi"))
    )
    (comp (ref "C96")
      (value "100nF X7R")
      (footprint "C-0805")
      (description "Ceramic Multilayer Capacitor")
      (fields (field (name "MANUFACTURER") "Yageo/Phycomp") (field (name "TOLERANCE") "±10%"))
      (libsource (lib "Hristo") (part "C semi"))
    )
    (comp (ref "C97")
      (value "390pF NP0")
      (footprint "C-0805")
      (description "Ceramic Multilayer Capacitor")
      (fields (field (name "MANUFACTURER") "Yageo/Phycomp") (field (name "TOLERANCE") "±10%"))
      (libsource (lib "Hristo") (part "C semi"))
    )
    (comp (ref "C98")
      (value "390pF NP0")
      (footprint "C-0805")
      (description "Ceramic Multilayer Capacitor")
      (fields (field (name "MANUFACTURER") "Yageo/Phycomp") (field (name "TOLERANCE") "±10%"))
      (libsource (lib "Hristo") (part "C semi"))
    )
    (comp (ref "C99")
      (value "100nF X7R")
      (footprint "C-0805")
      (description "Ceramic Multilayer Capacitor")
      (fields (field (name "MANUFACTURER") "Yageo/Phycomp") (field (name "TOLERANCE") "±10%"))
      (libsource (lib "Hristo") (part "C semi"))
    )
    (comp (ref "C100")
      (value "330pF NP0")
      (footprint "C-0805")
      (description "Ceramic Multilayer Capacitor")
      (fields (field (name "MANUFACTURER") "Yageo/Phycomp") (field (name "TOLERANCE") "±10%"))
      (libsource (lib "Hristo") (part "C semi"))
    )
    (comp (ref "D1")
      (value "BAV99LT1G")
      (footprint "FP-318-08-MFG")
      (description "DIODE ARRAY 100V 215MA SOT23-3")
      (libsource (lib "Altium Content Vault") (part "7b418a28e9680f52904df7990ac9ce6"))
    )
    (comp (ref "D2")
      (value "1N4148W-13-F")
      (footprint "FP-SOD123-MFG")
      (description "DIODE GEN PURP 100V 150MA SOD123")
      (fields
        (field (name "OCTOPART") "https://octopart.com/1n4148w-13-f-diodes+inc.-2359612")
        (field (name "MANUFACTURER") "Diodes Inc.")
      )
      (libsource (lib "Altium Content Vault") (part "d7152d700b627762746794eb795d46e"))
    )
    (comp (ref "D3")
      (value "1N4148W-13-F")
      (footprint "FP-SOD123-MFG")
      (description "DIODE GEN PURP 100V 150MA SOD123")
      (fields
        (field (name "OCTOPART") "https://octopart.com/1n4148w-13-f-diodes+inc.-2359612")
        (field (name "MANUFACTURER") "Diodes Inc.")
      )
      (libsource (lib "Altium Content Vault") (part "d7152d700b627762746794eb795d46e"))
    )
    (comp (ref "D4")
      (value "1N4148W-13-F")
      (footprint "FP-SOD123-MFG")
      (description "DIODE GEN PURP 100V 150MA SOD123")
      (fields
        (field (name "OCTOPART") "https://octopart.com/1n4148w-13-f-diodes+inc.-2359612")
        (field (name "MANUFACTURER") "Diodes Inc.")
      )
      (libsource (lib "Altium Content Vault") (part "d7152d700b627762746794eb795d46e"))
    )
    (comp (ref "D5")
      (value "1N4148W-13-F")
      (footprint "FP-SOD123-MFG")
      (description "DIODE GEN PURP 100V 150MA SOD123")
      (fields
        (field (name "OCTOPART") "https://octopart.com/1n4148w-13-f-diodes+inc.-2359612")
        (field (name "MANUFACTURER") "Diodes Inc.")
      )
      (libsource (lib "Altium Content Vault") (part "d7152d700b627762746794eb795d46e"))
    )
    (comp (ref "D6")
      (value "1N4148W-13-F")
      (footprint "FP-SOD123-MFG")
      (description "DIODE GEN PURP 100V 150MA SOD123")
      (fields
        (field (name "OCTOPART") "https://octopart.com/1n4148w-13-f-diodes+inc.-2359612")
        (field (name "MANUFACTURER") "Diodes Inc.")
      )
      (libsource (lib "Altium Content Vault") (part "d7152d700b627762746794eb795d46e"))
    )
    (comp (ref "D7")
      (value "1N4148W-13-F")
      (footprint "FP-SOD123-MFG")
      (description "DIODE GEN PURP 100V 150MA SOD123")
      (fields
        (field (name "OCTOPART") "https://octopart.com/1n4148w-13-f-diodes+inc.-2359612")
        (field (name "MANUFACTURER") "Diodes Inc.")
      )
      (libsource (lib "Altium Content Vault") (part "d7152d700b627762746794eb795d46e"))
    )
    (comp (ref "D8")
      (value "1N4148W-13-F")
      (footprint "FP-SOD123-MFG")
      (description "DIODE GEN PURP 100V 150MA SOD123")
      (fields
        (field (name "OCTOPART") "https://octopart.com/1n4148w-13-f-diodes+inc.-2359612")
        (field (name "MANUFACTURER") "Diodes Inc.")
      )
      (libsource (lib "Altium Content Vault") (part "d7152d700b627762746794eb795d46e"))
    )
    (comp (ref "D9")
      (value "1N4148W-13-F")
      (footprint "FP-SOD123-MFG")
      (description "DIODE GEN PURP 100V 150MA SOD123")
      (fields
        (field (name "OCTOPART") "https://octopart.com/1n4148w-13-f-diodes+inc.-2359612")
        (field (name "MANUFACTURER") "Diodes Inc.")
      )
      (libsource (lib "Altium Content Vault") (part "d7152d700b627762746794eb795d46e"))
    )
    (comp (ref "D10")
      (value "1N4148W-13-F")
      (footprint "FP-SOD123-MFG")
      (description "DIODE GEN PURP 100V 150MA SOD123")
      (fields
        (field (name "OCTOPART") "https://octopart.com/1n4148w-13-f-diodes+inc.-2359612")
        (field (name "MANUFACTURER") "Diodes Inc.")
      )
      (libsource (lib "Altium Content Vault") (part "d7152d700b627762746794eb795d46e"))
    )
    (comp (ref "D11")
      (value "1N4148W-13-F")
      (footprint "FP-SOD123-MFG")
      (description "DIODE GEN PURP 100V 150MA SOD123")
      (fields
        (field (name "OCTOPART") "https://octopart.com/1n4148w-13-f-diodes+inc.-2359612")
        (field (name "MANUFACTURER") "Diodes Inc.")
      )
      (libsource (lib "Altium Content Vault") (part "d7152d700b627762746794eb795d46e"))
    )
    (comp (ref "D12")
      (value "1N4148W-13-F")
      (footprint "FP-SOD123-MFG")
      (description "DIODE GEN PURP 100V 150MA SOD123")
      (fields
        (field (name "OCTOPART") "https://octopart.com/1n4148w-13-f-diodes+inc.-2359612")
        (field (name "MANUFACTURER") "Diodes Inc.")
      )
      (libsource (lib "Altium Content Vault") (part "d7152d700b627762746794eb795d46e"))
    )
    (comp (ref "D13")
      (value "1N4148W-13-F")
      (footprint "FP-SOD123-MFG")
      (description "DIODE GEN PURP 100V 150MA SOD123")
      (fields
        (field (name "OCTOPART") "https://octopart.com/1n4148w-13-f-diodes+inc.-2359612")
        (field (name "MANUFACTURER") "Diodes Inc.")
      )
      (libsource (lib "Altium Content Vault") (part "d7152d700b627762746794eb795d46e"))
    )
    (comp (ref "D14")
      (value "1N4148W-13-F")
      (footprint "FP-SOD123-MFG")
      (description "DIODE GEN PURP 100V 150MA SOD123")
      (fields
        (field (name "OCTOPART") "https://octopart.com/1n4148w-13-f-diodes+inc.-2359612")
        (field (name "MANUFACTURER") "Diodes Inc.")
      )
      (libsource (lib "Altium Content Vault") (part "d7152d700b627762746794eb795d46e"))
    )
    (comp (ref "D15")
      (value "1N4148W-13-F")
      (footprint "FP-SOD123-MFG")
      (description "DIODE GEN PURP 100V 150MA SOD123")
      (fields
        (field (name "OCTOPART") "https://octopart.com/1n4148w-13-f-diodes+inc.-2359612")
        (field (name "MANUFACTURER") "Diodes Inc.")
      )
      (libsource (lib "Altium Content Vault") (part "d7152d700b627762746794eb795d46e"))
    )
    (comp (ref "D16")
      (value "1N4148W-13-F")
      (footprint "FP-SOD123-MFG")
      (description "DIODE GEN PURP 100V 150MA SOD123")
      (fields
        (field (name "OCTOPART") "https://octopart.com/1n4148w-13-f-diodes+inc.-2359612")
        (field (name "MANUFACTURER") "Diodes Inc.")
      )
      (libsource (lib "Altium Content Vault") (part "d7152d700b627762746794eb795d46e"))
    )
    (comp (ref "F1") (value "RHP-44+") (footprint "GP731") (libsource (lib "Hristo") (part "RHP-44+")))
    (comp (ref "F2") (value "RLP-70+") (footprint "GP731") (libsource (lib "Hristo") (part "RLP-70+")))
    (comp (ref "IC1")
      (value "PGA103+/SPF5189Z")
      (footprint "SamacSys:SPF5189Z")
      (description "Integrated Circuit")
      (fields (field (name "MANUFACTURER_PART_NUMBER") "SPF5189Z"))
      (libsource (lib "*") (part "SPF5189Z"))
    )
    (comp (ref "IC2")
      (value "PE4312C-Z")
      (footprint "SamacSys:QFN50P400X400X90-21N-D")
      (description "Integrated Circuit")
      (libsource (lib "*") (part "PE4312C-Z"))
    )
    (comp (ref "IC3")
      (value "STPIC6C595TTR")
      (footprint "SamacSys:SOP65P640X120-16N")
      (description "Integrated Circuit")
      (fields (field (name "MOUSER PART NUMBER") "511-STPIC6C595T"))
      (libsource (lib "*") (part "STPIC6C595TTR"))
    )
    (comp (ref "IC4")
      (value "STPIC6C595TTR")
      (footprint "SamacSys:SOP65P640X120-16N")
      (description "Integrated Circuit")
      (fields (field (name "MOUSER PART NUMBER") "511-STPIC6C595T"))
      (libsource (lib "") (part "STPIC6C595TTR_1"))
    )
    (comp (ref "IC5")
      (value "STPIC6C595TTR")
      (footprint "SamacSys:SOP65P640X120-16N")
      (description "Integrated Circuit")
      (fields (field (name "MOUSER PART NUMBER") "511-STPIC6C595T"))
      (libsource (lib "*") (part "STPIC6C595TTR"))
    )
    (comp (ref "IC6")
      (value "TPS70933DBVR")
      (footprint "SamacSys:SOT95P280X145-5N")
      (description "Integrated Circuit")
      (fields (field (name "MOUSER PART NUMBER") "595-TPS70933DBVR"))
      (libsource (lib "SamacSys") (part "TPS70933DBVR"))
    )
    (comp (ref "J1")
      (value "DAC")
      (footprint "31-5431")
      (description "SMA")
      (fields (field (name "Comment") "ADC"))
      (libsource (lib "RF-UNIT_1") (part "31-5431"))
    )
    (comp (ref "J2")
      (value "ADC")
      (footprint "31-5431")
      (description "SMA")
      (libsource (lib "RF-UNIT_1") (part "31-5431"))
    )
    (comp (ref "J3")
      (value "RF_IN/OUT")
      (footprint "31-5431")
      (description "SMA")
      (fields (field (name "Comment") "ADC"))
      (libsource (lib "RF-UNIT_1") (part "31-5431"))
    )
    (comp (ref "J4")
      (value "B4B-PH-K-S_LF__SN_")
      (footprint "SamacSys:SHDR4W50P0X200_1X4_990X450X600P")
      (description "Connector")
      (fields (field (name "MANUFACTURER_PART_NUMBER") "B4B-PH-K-S(LF)(SN)"))
      (libsource (lib "*") (part "B4B-PH-K-S_LF__SN_"))
    )
    (comp (ref "J5")
      (value "DF11-12DP-2DSA_24_")
      (footprint "SamacSys:SHDR12W60P200_2X6_1400X500X690P")
      (description "Connector")
      (fields
        (field (name "MANUFACTURER_PART_NUMBER") "DF11-12DP-2DSA(24)")
        (field (name "MOUSER PART NUMBER") "798-DF11-12DP-2DSA24")
      )
      (libsource (lib "*") (part "DF11-12DP-2DSA_24_"))
    )
    (comp (ref "J6")
      (value "DF11-12DP-2DSA_24_")
      (footprint "SamacSys:SHDR12W60P200_2X6_1400X500X690P")
      (description "Connector")
      (fields
        (field (name "MANUFACTURER_PART_NUMBER") "DF11-12DP-2DSA(24)")
        (field (name "MOUSER PART NUMBER") "798-DF11-12DP-2DSA24")
      )
      (libsource (lib "*") (part "DF11-12DP-2DSA_24_"))
    )
    (comp (ref "K1")
      (value "G5V-1-DC12")
      (footprint "SamacSys:G5V1DC12")
      (description "Relay or Contactor")
      (fields (field (name "MOUSER PART NUMBER") "653-G5V-1-DC12"))
      (libsource (lib "SamacSys") (part "G5V-1-DC12"))
    )
    (comp (ref "K2")
      (value "G5V-1-DC12")
      (footprint "SamacSys:G5V1DC12")
      (description "Relay or Contactor")
      (fields (field (name "MOUSER PART NUMBER") "653-G5V-1-DC12"))
      (libsource (lib "") (part "G5V-1-DC12_1"))
    )
    (comp (ref "K3")
      (value "G5V-1-DC12")
      (footprint "SamacSys:G5V1DC12")
      (description "Relay or Contactor")
      (fields (field (name "MOUSER PART NUMBER") "653-G5V-1-DC12"))
      (libsource (lib "SamacSys") (part "G5V-1-DC12"))
    )
    (comp (ref "K4")
      (value "G5V-1-DC12")
      (footprint "SamacSys:G5V1DC12")
      (description "Relay or Contactor")
      (fields (field (name "MOUSER PART NUMBER") "653-G5V-1-DC12"))
      (libsource (lib "") (part "G5V-1-DC12_1"))
    )
    (comp (ref "K5")
      (value "G5V-1-DC12")
      (footprint "SamacSys:G5V1DC12")
      (description "Relay or Contactor")
      (fields (field (name "MOUSER PART NUMBER") "653-G5V-1-DC12"))
      (libsource (lib "SamacSys") (part "G5V-1-DC12"))
    )
    (comp (ref "K6")
      (value "G5V-1-DC12")
      (footprint "SamacSys:G5V1DC12")
      (description "Relay or Contactor")
      (fields (field (name "MOUSER PART NUMBER") "653-G5V-1-DC12"))
      (libsource (lib "") (part "G5V-1-DC12_1"))
    )
    (comp (ref "K7")
      (value "2-1462037-3")
      (footprint "TECO-2-1462037-3_V")
      (description "Signal Relay, 2 A, 12 VDC, -40 to 85 degC, 8-Pin SMD, RoHS, Tape and Reel")
      (fields (field (name "MANUFACTURER") "TE Connectivity"))
      (libsource (lib "Altium Content Vault") (part "TECO-2-1462037-3"))
    )
    (comp (ref "K8")
      (value "G5V-1-DC12")
      (footprint "SamacSys:G5V1DC12")
      (description "Relay or Contactor")
      (fields (field (name "MOUSER PART NUMBER") "653-G5V-1-DC12"))
      (libsource (lib "SamacSys") (part "G5V-1-DC12"))
    )
    (comp (ref "K9")
      (value "G5V-1-DC12")
      (footprint "SamacSys:G5V1DC12")
      (description "Relay or Contactor")
      (fields (field (name "MOUSER PART NUMBER") "653-G5V-1-DC12"))
      (libsource (lib "") (part "G5V-1-DC12_1"))
    )
    (comp (ref "K10")
      (value "G5V-1-DC12")
      (footprint "SamacSys:G5V1DC12")
      (description "Relay or Contactor")
      (fields (field (name "MOUSER PART NUMBER") "653-G5V-1-DC12"))
      (libsource (lib "SamacSys") (part "G5V-1-DC12"))
    )
    (comp (ref "K11")
      (value "G5V-1-DC12")
      (footprint "SamacSys:G5V1DC12")
      (description "Relay or Contactor")
      (fields (field (name "MOUSER PART NUMBER") "653-G5V-1-DC12"))
      (libsource (lib "") (part "G5V-1-DC12_1"))
    )
    (comp (ref "K12")
      (value "2-1462037-3")
      (footprint "TECO-2-1462037-3_V")
      (description "Signal Relay, 2 A, 12 VDC, -40 to 85 degC, 8-Pin SMD, RoHS, Tape and Reel")
      (fields (field (name "MANUFACTURER") "TE Connectivity"))
      (libsource (lib "Altium Content Vault") (part "TECO-2-1462037-3"))
    )
    (comp (ref "K13")
      (value "G5V-1-DC12")
      (footprint "SamacSys:G5V1DC12")
      (description "Relay or Contactor")
      (fields (field (name "MOUSER PART NUMBER") "653-G5V-1-DC12"))
      (libsource (lib "SamacSys") (part "G5V-1-DC12"))
    )
    (comp (ref "K14")
      (value "G5V-1-DC12")
      (footprint "SamacSys:G5V1DC12")
      (description "Relay or Contactor")
      (fields (field (name "MOUSER PART NUMBER") "653-G5V-1-DC12"))
      (libsource (lib "SamacSys") (part "G5V-1-DC12"))
    )
    (comp (ref "K15")
      (value "G5V-1-DC12")
      (footprint "SamacSys:G5V1DC12")
      (description "Relay or Contactor")
      (fields (field (name "MOUSER PART NUMBER") "653-G5V-1-DC12"))
      (libsource (lib "") (part "G5V-1-DC12_1"))
    )
    (comp (ref "K16")
      (value "2-1462037-3")
      (footprint "TECO-2-1462037-3_V")
      (description "Signal Relay, 2 A, 12 VDC, -40 to 85 degC, 8-Pin SMD, RoHS, Tape and Reel")
      (fields (field (name "MANUFACTURER") "TE Connectivity"))
      (libsource (lib "Altium Content Vault") (part "TECO-2-1462037-3"))
    )
    (comp (ref "K17")
      (value "G5V-1-DC12")
      (footprint "SamacSys:G5V1DC12")
      (description "Relay or Contactor")
      (fields (field (name "MOUSER PART NUMBER") "653-G5V-1-DC12"))
      (libsource (lib "SamacSys") (part "G5V-1-DC12"))
    )
    (comp (ref "K18")
      (value "G5V-1-DC12")
      (footprint "SamacSys:G5V1DC12")
      (description "Relay or Contactor")
      (fields (field (name "MOUSER PART NUMBER") "653-G5V-1-DC12"))
      (libsource (lib "") (part "G5V-1-DC12_1"))
    )
    (comp (ref "K19")
      (value "G5V-1-DC12")
      (footprint "SamacSys:G5V1DC12")
      (description "Relay or Contactor")
      (fields (field (name "MOUSER PART NUMBER") "653-G5V-1-DC12"))
      (libsource (lib "SamacSys") (part "G5V-1-DC12"))
    )
    (comp (ref "K20")
      (value "G5V-1-DC12")
      (footprint "SamacSys:G5V1DC12")
      (description "Relay or Contactor")
      (fields (field (name "MOUSER PART NUMBER") "653-G5V-1-DC12"))
      (libsource (lib "") (part "G5V-1-DC12_1"))
    )
    (comp (ref "K21")
      (value "G5V-1-DC12")
      (footprint "SamacSys:G5V1DC12")
      (description "Relay or Contactor")
      (fields (field (name "MOUSER PART NUMBER") "653-G5V-1-DC12"))
      (libsource (lib "SamacSys") (part "G5V-1-DC12"))
    )
    (comp (ref "K22")
      (value "G5V-1-DC12")
      (footprint "SamacSys:G5V1DC12")
      (description "Relay or Contactor")
      (fields (field (name "MOUSER PART NUMBER") "653-G5V-1-DC12"))
      (libsource (lib "") (part "G5V-1-DC12_1"))
    )
    (comp (ref "K23")
      (value "G5V-1-DC12")
      (footprint "SamacSys:G5V1DC12")
      (description "Relay or Contactor")
      (fields (field (name "MOUSER PART NUMBER") "653-G5V-1-DC12"))
      (libsource (lib "SamacSys") (part "G5V-1-DC12"))
    )
    (comp (ref "K24")
      (value "G5V-1-DC12")
      (footprint "SamacSys:G5V1DC12")
      (description "Relay or Contactor")
      (fields (field (name "MOUSER PART NUMBER") "653-G5V-1-DC12"))
      (libsource (lib "") (part "G5V-1-DC12_1"))
    )
    (comp (ref "K25")
      (value "G5V-1-DC12")
      (footprint "SamacSys:G5V1DC12")
      (description "Relay or Contactor")
      (fields (field (name "MOUSER PART NUMBER") "653-G5V-1-DC12"))
      (libsource (lib "SamacSys") (part "G5V-1-DC12"))
    )
    (comp (ref "K26")
      (value "G5V-1-DC12")
      (footprint "SamacSys:G5V1DC12")
      (description "Relay or Contactor")
      (fields (field (name "MOUSER PART NUMBER") "653-G5V-1-DC12"))
      (libsource (lib "") (part "G5V-1-DC12_1"))
    )
    (comp (ref "K27")
      (value "G5V-1-DC12")
      (footprint "SamacSys:G5V1DC12")
      (description "Relay or Contactor")
      (fields (field (name "MOUSER PART NUMBER") "653-G5V-1-DC12"))
      (libsource (lib "SamacSys") (part "G5V-1-DC12"))
    )
    (comp (ref "K28")
      (value "G5V-1-DC12")
      (footprint "SamacSys:G5V1DC12")
      (description "Relay or Contactor")
      (fields (field (name "MOUSER PART NUMBER") "653-G5V-1-DC12"))
      (libsource (lib "") (part "G5V-1-DC12_1"))
    )
    (comp (ref "L1")
      (value "RF_inductor")
      (footprint "L-2520")
      (libsource (lib "Hristo") (part "RF_inductor"))
    )
    (comp (ref "L2")
      (value "RF_inductor")
      (footprint "L-2520")
      (libsource (lib "Hristo") (part "RF_inductor"))
    )
    (comp (ref "L3")
      (value "RF_inductor")
      (footprint "3.81x3.43x4.95")
      (libsource (lib "Hristo") (part "RF_inductor"))
    )
    (comp (ref "L4")
      (value "RF_inductor")
      (footprint "3.81x3.43x4.95")
      (libsource (lib "Hristo") (part "RF_inductor"))
    )
    (comp (ref "L5")
      (value "RF_inductor")
      (footprint "3.81x3.43x4.95")
      (libsource (lib "Hristo") (part "RF_inductor"))
    )
    (comp (ref "L6")
      (value "RF_inductor")
      (footprint "L-0805")
      (libsource (lib "Hristo") (part "RF_inductor"))
    )
    (comp (ref "L7")
      (value "RF_inductor")
      (footprint "L-0805")
      (libsource (lib "Hristo") (part "RF_inductor"))
    )
    (comp (ref "L8")
      (value "RF_inductor")
      (footprint "L-0805")
      (libsource (lib "Hristo") (part "RF_inductor"))
    )
    (comp (ref "L9")
      (value "CB2012T101K")
      (footprint "FP-CB2012-MFG")
      (description "SMD Inductors 100uH ±10% 0.13A 9.1Ω 0805")
      (fields (field (name "TOLERANCE") "10%"))
      (libsource (lib "Altium Content Vault") (part "725321dda6339637d4d059423bc1c3c"))
    )
    (comp (ref "L10")
      (value "CB2012T101K")
      (footprint "FP-CB2012-MFG")
      (description "SMD Inductors 100uH ±10% 0.13A 9.1Ω 0805")
      (fields (field (name "TOLERANCE") "10%"))
      (libsource (lib "Altium Content Vault") (part "725321dda6339637d4d059423bc1c3c"))
    )
    (comp (ref "L11")
      (value "LQM21NNR22K10D")
      (footprint "FP-LQM21DN_00-IPC_C")
      (description "Multilayer Type Inductor for General Circuits, 0805 (2012), 0.22μH, 10%, 0.38Ω, 250mA")
      (fields (field (name "TOLERANCE") "10%"))
      (libsource (lib "Altium Content Vault") (part "725321dda6339637d4d059423bc1c3c"))
    )
    (comp (ref "L12")
      (value "CB2012T101K")
      (footprint "FP-CB2012-MFG")
      (description "SMD Inductors 100uH ±10% 0.13A 9.1Ω 0805")
      (fields (field (name "TOLERANCE") "10%"))
      (libsource (lib "Altium Content Vault") (part "725321dda6339637d4d059423bc1c3c"))
    )
    (comp (ref "L13") (value "0.64uH") (footprint "Amidon_T50_6") (libsource (lib "Hristo") (part "Amidon")))
    (comp (ref "L14") (value "0.64uH") (footprint "Amidon_T50_6") (libsource (lib "Hristo") (part "Amidon")))
    (comp (ref "L15") (value "0.64uH") (footprint "Amidon_T50_6") (libsource (lib "Hristo") (part "Amidon")))
    (comp (ref "L16")
      (value "CB2012T101K")
      (footprint "FP-CB2012-MFG")
      (description "SMD Inductors 100uH ±10% 0.13A 9.1Ω 0805")
      (fields (field (name "TOLERANCE") "10%"))
      (libsource (lib "Altium Content Vault") (part "725321dda6339637d4d059423bc1c3c"))
    )
    (comp (ref "L17") (value "0.82uH") (footprint "Amidon_T50_6") (libsource (lib "Hristo") (part "Amidon")))
    (comp (ref "L18") (value "0.82uH") (footprint "Amidon_T50_6") (libsource (lib "Hristo") (part "Amidon")))
    (comp (ref "L19") (value "0.82uH") (footprint "Amidon_T50_6") (libsource (lib "Hristo") (part "Amidon")))
    (comp (ref "L20")
      (value "CB2012T101K")
      (footprint "FP-CB2012-MFG")
      (description "SMD Inductors 100uH ±10% 0.13A 9.1Ω 0805")
      (fields (field (name "TOLERANCE") "10%"))
      (libsource (lib "Altium Content Vault") (part "725321dda6339637d4d059423bc1c3c"))
    )
    (comp (ref "L21") (value "1.0uH") (footprint "Amidon_T50_6") (libsource (lib "Hristo") (part "Amidon")))
    (comp (ref "L22") (value "1.0uH") (footprint "Amidon_T50_6") (libsource (lib "Hristo") (part "Amidon")))
    (comp (ref "L23")
      (value "CB2012T101K")
      (footprint "FP-CB2012-MFG")
      (description "SMD Inductors 100uH ±10% 0.13A 9.1Ω 0805")
      (fields (field (name "TOLERANCE") "10%"))
      (libsource (lib "Altium Content Vault") (part "725321dda6339637d4d059423bc1c3c"))
    )
    (comp (ref "L24") (value "1.0uH") (footprint "Amidon_T50_6") (libsource (lib "Hristo") (part "Amidon")))
    (comp (ref "L25")
      (value "CB2012T101K")
      (footprint "FP-CB2012-MFG")
      (description "SMD Inductors 100uH ±10% 0.13A 9.1Ω 0805")
      (fields (field (name "TOLERANCE") "10%"))
      (libsource (lib "Altium Content Vault") (part "725321dda6339637d4d059423bc1c3c"))
    )
    (comp (ref "L26") (value "1.7uH") (footprint "Amidon_T50_6") (libsource (lib "Hristo") (part "Amidon")))
    (comp (ref "L27") (value "1.7uH") (footprint "Amidon_T50_6") (libsource (lib "Hristo") (part "Amidon")))
    (comp (ref "L28") (value "1.7uH") (footprint "Amidon_T50_6") (libsource (lib "Hristo") (part "Amidon")))
    (comp (ref "L29")
      (value "CB2012T101K")
      (footprint "FP-CB2012-MFG")
      (description "SMD Inductors 100uH ±10% 0.13A 9.1Ω 0805")
      (fields (field (name "TOLERANCE") "10%"))
      (libsource (lib "Altium Content Vault") (part "725321dda6339637d4d059423bc1c3c"))
    )
    (comp (ref "L30") (value "2.0uH") (footprint "Amidon_T50_2") (libsource (lib "Hristo") (part "Amidon")))
    (comp (ref "L31") (value "2.0uH") (footprint "Amidon_T50_2") (libsource (lib "Hristo") (part "Amidon")))
    (comp (ref "L32") (value "2.0uH") (footprint "Amidon_T50_2") (libsource (lib "Hristo") (part "Amidon")))
    (comp (ref "L33")
      (value "CB2012T101K")
      (footprint "FP-CB2012-MFG")
      (description "SMD Inductors 100uH ±10% 0.13A 9.1Ω 0805")
      (fields (field (name "TOLERANCE") "10%"))
      (libsource (lib "Altium Content Vault") (part "725321dda6339637d4d059423bc1c3c"))
    )
    (comp (ref "L34") (value "3.75uH") (footprint "Amidon_T50_2") (libsource (lib "Hristo") (part "Amidon")))
    (comp (ref "L35") (value "3.75uH") (footprint "Amidon_T50_2") (libsource (lib "Hristo") (part "Amidon")))
    (comp (ref "L36") (value "3.75uH") (footprint "Amidon_T50_2") (libsource (lib "Hristo") (part "Amidon")))
    (comp (ref "L37")
      (value "CB2012T101K")
      (footprint "FP-CB2012-MFG")
      (description "SMD Inductors 100uH ±10% 0.13A 9.1Ω 0805")
      (fields (field (name "TOLERANCE") "10%"))
      (libsource (lib "Altium Content Vault") (part "725321dda6339637d4d059423bc1c3c"))
    )
    (comp (ref "L38") (value "5.3uH") (footprint "Amidon_FT50_6x") (libsource (lib "Hristo") (part "Amidon")))
    (comp (ref "L39") (value "5.3uH") (footprint "Amidon_FT50_6x") (libsource (lib "Hristo") (part "Amidon")))
    (comp (ref "L40") (value "5.3uH") (footprint "Amidon_FT50_6x") (libsource (lib "Hristo") (part "Amidon")))
    (comp (ref "L41")
      (value "CB2012T101K")
      (footprint "FP-CB2012-MFG")
      (description "SMD Inductors 100uH ±10% 0.13A 9.1Ω 0805")
      (fields (field (name "TOLERANCE") "10%"))
      (libsource (lib "Altium Content Vault") (part "725321dda6339637d4d059423bc1c3c"))
    )
    (comp (ref "L42") (value "7.1uH") (footprint "Amidon_FT50_6x") (libsource (lib "Hristo") (part "Amidon")))
    (comp (ref "L43") (value "7.1uH") (footprint "Amidon_FT50_6x") (libsource (lib "Hristo") (part "Amidon")))
    (comp (ref "L44") (value "7.1uH") (footprint "Amidon_FT50_6x") (libsource (lib "Hristo") (part "Amidon")))
    (comp (ref "L45")
      (value "CB2012T101K")
      (footprint "FP-CB2012-MFG")
      (description "SMD Inductors 100uH ±10% 0.13A 9.1Ω 0805")
      (fields (field (name "TOLERANCE") "10%"))
      (libsource (lib "Altium Content Vault") (part "725321dda6339637d4d059423bc1c3c"))
    )
    (comp (ref "L46") (value "9.5uH") (footprint "Amidon_FT50_6x") (libsource (lib "Hristo") (part "Amidon")))
    (comp (ref "L47") (value "9.5uH") (footprint "Amidon_FT50_6x") (libsource (lib "Hristo") (part "Amidon")))
    (comp (ref "L48") (value "9.5uH") (footprint "Amidon_FT50_6x") (libsource (lib "Hristo") (part "Amidon")))
    (comp (ref "L49")
      (value "CB2012T101K")
      (footprint "FP-CB2012-MFG")
      (description "SMD Inductors 100uH ±10% 0.13A 9.1Ω 0805")
      (fields (field (name "TOLERANCE") "10%"))
      (libsource (lib "Altium Content Vault") (part "725321dda6339637d4d059423bc1c3c"))
    )
    (comp (ref "M1") (value "MountHole") (footprint "MountHole") (libsource (lib "Sch") (part "MountHole")))
    (comp (ref "M2") (value "MountHole") (footprint "MountHole") (libsource (lib "Sch") (part "MountHole")))
    (comp (ref "M3") (value "MountHole") (footprint "MountHole") (libsource (lib "Sch") (part "MountHole")))
    (comp (ref "M4") (value "MountHole") (footprint "MountHole") (libsource (lib "Sch") (part "MountHole")))
    (comp (ref "Q1")
      (value "IRLML9301TRPBF")
      (footprint "INF-SOT-23-3_V")
      (description "HEXFET(R) Power MOSFET, 3.6 A, 30 V, -55 to 150 degC, 3-Pin SOT-23, RoHS, Tape and Reel")
      (fields (field (name "MANUFACTURER") "InfineonTechnologies"))
      (libsource (lib "Altium Content Vault") (part "PEMOS-GSD-3"))
    )
    (comp (ref "R1")
      (value "18R")
      (footprint "R-0603")
      (description "Chip Resistor")
      (fields (field (name "MANUFACTURER") "Yageo/Phycomp"))
      (libsource (lib "Hristo") (part "RES semi"))
    )
    (comp (ref "R2")
      (value "1k")
      (footprint "R-0603")
      (description "Chip Resistor")
      (fields (field (name "MANUFACTURER") "Yageo/Phycomp"))
      (libsource (lib "Hristo") (part "RES semi"))
    )
    (comp (ref "R3")
      (value "30k")
      (footprint "R-0603")
      (description "Chip Resistor")
      (fields (field (name "MANUFACTURER") "Yageo/Phycomp"))
      (libsource (lib "Hristo") (part "RES semi"))
    )
    (comp (ref "R4")
      (value "1k")
      (footprint "R-0603")
      (description "Chip Resistor")
      (fields (field (name "MANUFACTURER") "Yageo/Phycomp"))
      (libsource (lib "Hristo") (part "RES semi"))
    )
    (comp (ref "R5")
      (value "1k")
      (footprint "R-0603")
      (description "Chip Resistor")
      (fields (field (name "MANUFACTURER") "Yageo/Phycomp"))
      (libsource (lib "Hristo") (part "RES semi"))
    )
    (comp (ref "R6")
      (value "1k")
      (footprint "R-0603")
      (description "Chip Resistor")
      (fields (field (name "MANUFACTURER") "Yageo/Phycomp"))
      (libsource (lib "Hristo") (part "RES semi"))
    )
    (comp (ref "R7")
      (value "1k")
      (footprint "R-0603")
      (description "Chip Resistor")
      (fields (field (name "MANUFACTURER") "Yageo/Phycomp"))
      (libsource (lib "Hristo") (part "RES semi"))
    )
    (comp (ref "R8")
      (value "1k")
      (footprint "R-0603")
      (description "Chip Resistor")
      (fields (field (name "MANUFACTURER") "Yageo/Phycomp"))
      (libsource (lib "Hristo") (part "RES semi"))
    )
    (comp (ref "R9")
      (value "1k")
      (footprint "R-0603")
      (description "Chip Resistor")
      (fields (field (name "MANUFACTURER") "Yageo/Phycomp"))
      (libsource (lib "Hristo") (part "RES semi"))
    )
    (comp (ref "U1")
      (value "TPS79650DCQR")
      (footprint "DCQ0006A_L")
      (fields (field (name "MANUFACTURER") "Texas Instruments"))
      (libsource (lib "Altium Content Vault") (part "TI-TPS7XXXXXXXX"))
    )
  )
  (nets
    (net (code "1") (name "+3.3V") (class "Default")
      (node (ref "C45") (pin "1") (pinfunction "1_1") (pintype "passive"))
      (node (ref "C47") (pin "1") (pinfunction "1_1") (pintype "passive"))
      (node (ref "C55") (pin "1") (pinfunction "1_1") (pintype "passive"))
      (node (ref "C63") (pin "1") (pinfunction "1_1") (pintype "passive"))
      (node (ref "C78") (pin "1") (pinfunction "1_1") (pintype "passive"))
      (node (ref "C85") (pin "2") (pinfunction "2_2") (pintype "passive"))
      (node (ref "C86") (pin "2") (pinfunction "2_2") (pintype "passive"))
      (node (ref "IC2") (pin "5") (pinfunction "LE_5") (pintype "passive"))
      (node (ref "IC2") (pin "6") (pinfunction "VDD_1_6") (pintype "passive"))
      (node (ref "IC2") (pin "9") (pinfunction "VDD_2_9") (pintype "passive"))
      (node (ref "IC3") (pin "1") (pinfunction "VCC_1") (pintype "passive"))
      (node (ref "IC3") (pin "7") (pinfunction "~{CLR}_7") (pintype "passive"))
      (node (ref "IC4") (pin "1") (pinfunction "VCC_1") (pintype "passive"))
      (node (ref "IC4") (pin "7") (pinfunction "~{CLR}_7") (pintype "passive"))
      (node (ref "IC5") (pin "1") (pinfunction "VCC_1") (pintype "passive"))
      (node (ref "IC5") (pin "7") (pinfunction "~{CLR}_7") (pintype "passive"))
      (node (ref "IC6") (pin "5") (pinfunction "OUT_5") (pintype "passive"))
      (node (ref "R2") (pin "2") (pinfunction "2_2") (pintype "passive"))
      (node (ref "R4") (pin "2") (pinfunction "2_2") (pintype "passive"))
      (node (ref "R5") (pin "2") (pinfunction "2_2") (pintype "passive"))
      (node (ref "R6") (pin "2") (pinfunction "2_2") (pintype "passive"))
      (node (ref "R7") (pin "2") (pinfunction "2_2") (pintype "passive"))
      (node (ref "R8") (pin "2") (pinfunction "2_2") (pintype "passive"))
      (node (ref "R9") (pin "2") (pinfunction "2_2") (pintype "passive"))
    )
    (net (code "2") (name "+5V") (class "Default")
      (node (ref "C19") (pin "2") (pinfunction "2_2") (pintype "passive"))
      (node (ref "C20") (pin "2") (pinfunction "2_2") (pintype "passive"))
      (node (ref "C74") (pin "2") (pinfunction "2_2") (pintype "passive"))
      (node (ref "C75") (pin "2") (pinfunction "2_2") (pintype "passive"))
      (node (ref "R1") (pin "2") (pinfunction "2_2") (pintype "passive"))
      (node (ref "U1") (pin "4") (pinfunction "OUT_4") (pintype "power_in"))
    )
    (net (code "3") (name "+12V") (class "Default")
      (node (ref "C13") (pin "2") (pinfunction "2_2") (pintype "passive"))
      (node (ref "C14") (pin "2") (pinfunction "2_2") (pintype "passive"))
      (node (ref "C16") (pin "2") (pinfunction "2_2") (pintype "passive"))
      (node (ref "C17") (pin "2") (pinfunction "2_2") (pintype "passive"))
      (node (ref "C23") (pin "2") (pinfunction "2_2") (pintype "passive"))
      (node (ref "C24") (pin "2") (pinfunction "2_2") (pintype "passive"))
      (node (ref "C27") (pin "2") (pinfunction "2_2") (pintype "passive"))
      (node (ref "C31") (pin "2") (pinfunction "2_2") (pintype "passive"))
      (node (ref "C34") (pin "2") (pinfunction "2_2") (pintype "passive"))
      (node (ref "C38") (pin "2") (pinfunction "2_2") (pintype "passive"))
      (node (ref "C39") (pin "2") (pinfunction "2_2") (pintype "passive"))
      (node (ref "C40") (pin "2") (pinfunction "2_2") (pintype "passive"))
      (node (ref "C41") (pin "2") (pinfunction "2_2") (pintype "passive"))
      (node (ref "C44") (pin "2") (pinfunction "2_2") (pintype "passive"))
      (node (ref "C50") (pin "2") (pinfunction "2_2") (pintype "passive"))
      (node (ref "C53") (pin "2") (pinfunction "2_2") (pintype "passive"))
      (node (ref "C58") (pin "2") (pinfunction "2_2") (pintype "passive"))
      (node (ref "C61") (pin "2") (pinfunction "2_2") (pintype "passive"))
      (node (ref "C66") (pin "2") (pinfunction "2_2") (pintype "passive"))
      (node (ref "C69") (pin "2") (pinfunction "2_2") (pintype "passive"))
      (node (ref "C71") (pin "1") (pinfunction "+_1") (pintype "passive"))
      (node (ref "C79") (pin "2") (pinfunction "2_2") (pintype "passive"))
      (node (ref "C8") (pin "2") (pinfunction "2_2") (pintype "passive"))
      (node (ref "C82") (pin "2") (pinfunction "2_2") (pintype "passive"))
      (node (ref "C84") (pin "2") (pinfunction "2_2") (pintype "passive"))
      (node (ref "C89") (pin "2") (pinfunction "2_2") (pintype "passive"))
      (node (ref "C9") (pin "2") (pinfunction "2_2") (pintype "passive"))
      (node (ref "C92") (pin "2") (pinfunction "2_2") (pintype "passive"))
      (node (ref "C96") (pin "2") (pinfunction "2_2") (pintype "passive"))
      (node (ref "C99") (pin "2") (pinfunction "2_2") (pintype "passive"))
      (node (ref "D10") (pin "1") (pinfunction "C_1") (pintype "passive"))
      (node (ref "D11") (pin "1") (pinfunction "C_1") (pintype "passive"))
      (node (ref "D12") (pin "1") (pinfunction "C_1") (pintype "passive"))
      (node (ref "D13") (pin "1") (pinfunction "C_1") (pintype "passive"))
      (node (ref "D14") (pin "1") (pinfunction "C_1") (pintype "passive"))
      (node (ref "D15") (pin "1") (pinfunction "C_1") (pintype "passive"))
      (node (ref "D16") (pin "1") (pinfunction "C_1") (pintype "passive"))
      (node (ref "D2") (pin "1") (pinfunction "C_1") (pintype "passive"))
      (node (ref "D3") (pin "1") (pinfunction "C_1") (pintype "passive"))
      (node (ref "D4") (pin "1") (pinfunction "C_1") (pintype "passive"))
      (node (ref "D5") (pin "1") (pinfunction "C_1") (pintype "passive"))
      (node (ref "D6") (pin "1") (pinfunction "C_1") (pintype "passive"))
      (node (ref "D7") (pin "1") (pinfunction "C_1") (pintype "passive"))
      (node (ref "D8") (pin "1") (pinfunction "C_1") (pintype "passive"))
      (node (ref "D9") (pin "1") (pinfunction "C_1") (pintype "passive"))
      (node (ref "IC6") (pin "1") (pinfunction "IN_1") (pintype "passive"))
      (node (ref "IC6") (pin "3") (pinfunction "EN_3") (pintype "passive"))
      (node (ref "J4") (pin "3") (pinfunction "3_3") (pintype "passive"))
      (node (ref "J4") (pin "4") (pinfunction "4_4") (pintype "passive"))
      (node (ref "K1") (pin "2") (pinfunction "COIL_1_2") (pintype "input"))
      (node (ref "K10") (pin "2") (pinfunction "COIL_1_2") (pintype "input"))
      (node (ref "K11") (pin "9") (pinfunction "COIL_2_9") (pintype "power_in"))
      (node (ref "K12") (pin "8") (pinfunction "8_8") (pintype "passive"))
      (node (ref "K13") (pin "2") (pinfunction "COIL_1_2") (pintype "input"))
      (node (ref "K14") (pin "2") (pinfunction "COIL_1_2") (pintype "input"))
      (node (ref "K15") (pin "9") (pinfunction "COIL_2_9") (pintype "power_in"))
      (node (ref "K16") (pin "8") (pinfunction "8_8") (pintype "passive"))
      (node (ref "K17") (pin "2") (pinfunction "COIL_1_2") (pintype "input"))
      (node (ref "K18") (pin "9") (pinfunction "COIL_2_9") (pintype "power_in"))
      (node (ref "K19") (pin "2") (pinfunction "COIL_1_2") (pintype "input"))
      (node (ref "K2") (pin "9") (pinfunction "COIL_2_9") (pintype "power_in"))
      (node (ref "K20") (pin "9") (pinfunction "COIL_2_9") (pintype "power_in"))
      (node (ref "K21") (pin "2") (pinfunction "COIL_1_2") (pintype "input"))
      (node (ref "K22") (pin "9") (pinfunction "COIL_2_9") (pintype "power_in"))
      (node (ref "K23") (pin "2") (pinfunction "COIL_1_2") (pintype "input"))
      (node (ref "K24") (pin "9") (pinfunction "COIL_2_9") (pintype "power_in"))
      (node (ref "K25") (pin "2") (pinfunction "COIL_1_2") (pintype "input"))
      (node (ref "K26") (pin "9") (pinfunction "COIL_2_9") (pintype "power_in"))
      (node (ref "K27") (pin "2") (pinfunction "COIL_1_2") (pintype "input"))
      (node (ref "K28") (pin "9") (pinfunction "COIL_2_9") (pintype "power_in"))
      (node (ref "K3") (pin "2") (pinfunction "COIL_1_2") (pintype "input"))
      (node (ref "K4") (pin "9") (pinfunction "COIL_2_9") (pintype "power_in"))
      (node (ref "K5") (pin "2") (pinfunction "COIL_1_2") (pintype "input"))
      (node (ref "K6") (pin "9") (pinfunction "COIL_2_9") (pintype "power_in"))
      (node (ref "K7") (pin "8") (pinfunction "8_8") (pintype "passive"))
      (node (ref "K8") (pin "2") (pinfunction "COIL_1_2") (pintype "input"))
      (node (ref "K9") (pin "9") (pinfunction "COIL_2_9") (pintype "power_in"))
      (node (ref "Q1") (pin "2") (pinfunction "SOURCE_2") (pintype "passive"))
      (node (ref "R3") (pin "1") (pinfunction "1_1") (pintype "passive"))
    )
    (net (code "4") (name "/ADC") (class "Default")
      (node (ref "J2") (pin "5") (pinfunction "CON_5") (pintype "passive"))
      (node (ref "K13") (pin "1") (pinfunction "NC_1") (pintype "passive"))
    )
    (net (code "5") (name "/ATT_0.5") (class "Default")
      (node (ref "IC2") (pin "20") (pinfunction "C0.5_20") (pintype "passive"))
      (node (ref "IC5") (pin "3") (pinfunction "DRAIN0_3") (pintype "passive"))
      (node (ref "R6") (pin "1") (pinfunction "1_1") (pintype "passive"))
    )
    (net (code "6") (name "/ATT_1") (class "Default")
      (node (ref "IC2") (pin "19") (pinfunction "C1_19") (pintype "passive"))
      (node (ref "IC5") (pin "4") (pinfunction "DRAIN1_4") (pintype "passive"))
      (node (ref "R7") (pin "1") (pinfunction "1_1") (pintype "passive"))
    )
    (net (code "7") (name "/ATT_2") (class "Default")
      (node (ref "IC2") (pin "17") (pinfunction "C2_17") (pintype "passive"))
      (node (ref "IC5") (pin "5") (pinfunction "DRAIN2_5") (pintype "passive"))
      (node (ref "R8") (pin "1") (pinfunction "1_1") (pintype "passive"))
    )
    (net (code "8") (name "/ATT_4") (class "Default")
      (node (ref "IC2") (pin "16") (pinfunction "C4_16") (pintype "passive"))
      (node (ref "IC5") (pin "6") (pinfunction "DRAIN3_6") (pintype "passive"))
      (node (ref "R9") (pin "1") (pinfunction "1_1") (pintype "passive"))
    )
    (net (code "9") (name "/ATT_8") (class "Default")
      (node (ref "IC2") (pin "15") (pinfunction "C8_15") (pintype "passive"))
      (node (ref "IC5") (pin "11") (pinfunction "DRAIN4_11") (pintype "passive"))
      (node (ref "R5") (pin "1") (pinfunction "1_1") (pintype "passive"))
    )
    (net (code "10") (name "/ATT_16") (class "Default")
      (node (ref "IC2") (pin "1") (pinfunction "C16_1") (pintype "passive"))
      (node (ref "IC5") (pin "12") (pinfunction "DRAIN5_12") (pintype "passive"))
      (node (ref "R4") (pin "1") (pinfunction "1_1") (pintype "passive"))
    )
    (net (code "11") (name "/BPF_IN") (class "Default")
      (node (ref "K1") (pin "10") (pinfunction "NO_10") (pintype "passive"))
      (node (ref "K10") (pin "10") (pinfunction "NO_10") (pintype "passive"))
      (node (ref "K14") (pin "10") (pinfunction "NO_10") (pintype "passive"))
      (node (ref "K16") (pin "6") (pinfunction "6_6") (pintype "passive"))
      (node (ref "K17") (pin "10") (pinfunction "NO_10") (pintype "passive"))
      (node (ref "K19") (pin "10") (pinfunction "NO_10") (pintype "passive"))
      (node (ref "K21") (pin "10") (pinfunction "NO_10") (pintype "passive"))
      (node (ref "K23") (pin "10") (pinfunction "NO_10") (pintype "passive"))
      (node (ref "K25") (pin "10") (pinfunction "NO_10") (pintype "passive"))
      (node (ref "K27") (pin "10") (pinfunction "NO_10") (pintype "passive"))
      (node (ref "K3") (pin "10") (pinfunction "NO_10") (pintype "passive"))
      (node (ref "K5") (pin "10") (pinfunction "NO_10") (pintype "passive"))
      (node (ref "K8") (pin "10") (pinfunction "NO_10") (pintype "passive"))
    )
    (net (code "12") (name "/BPF_OFF") (class "Default")
      (node (ref "C13") (pin "1") (pinfunction "1_1") (pintype "passive"))
      (node (ref "D13") (pin "2") (pinfunction "A_2") (pintype "passive"))
      (node (ref "IC4") (pin "6") (pinfunction "DRAIN3_6") (pintype "passive"))
      (node (ref "K3") (pin "9") (pinfunction "COIL_2_9") (pintype "power_in"))
      (node (ref "L10") (pin "1") (pinfunction "1_1") (pintype "passive"))
    )
    (net (code "13") (name "/BPF_OUT") (class "Default")
      (node (ref "K11") (pin "10") (pinfunction "NO_10") (pintype "passive"))
      (node (ref "K13") (pin "6") (pinfunction "COM_2_6") (pintype "passive"))
      (node (ref "K15") (pin "10") (pinfunction "NO_10") (pintype "passive"))
      (node (ref "K18") (pin "10") (pinfunction "NO_10") (pintype "passive"))
      (node (ref "K2") (pin "10") (pinfunction "NO_10") (pintype "passive"))
      (node (ref "K20") (pin "10") (pinfunction "NO_10") (pintype "passive"))
      (node (ref "K22") (pin "10") (pinfunction "NO_10") (pintype "passive"))
      (node (ref "K24") (pin "10") (pinfunction "NO_10") (pintype "passive"))
      (node (ref "K26") (pin "10") (pinfunction "NO_10") (pintype "passive"))
      (node (ref "K28") (pin "10") (pinfunction "NO_10") (pintype "passive"))
      (node (ref "K4") (pin "10") (pinfunction "NO_10") (pintype "passive"))
      (node (ref "K6") (pin "10") (pinfunction "NO_10") (pintype "passive"))
      (node (ref "K9") (pin "10") (pinfunction "NO_10") (pintype "passive"))
    )
    (net (code "14") (name "/BPF_OUT0") (class "Default")
      (node (ref "C8") (pin "1") (pinfunction "1_1") (pintype "passive"))
      (node (ref "D2") (pin "2") (pinfunction "A_2") (pintype "passive"))
      (node (ref "IC3") (pin "3") (pinfunction "DRAIN0_3") (pintype "passive"))
      (node (ref "K1") (pin "9") (pinfunction "COIL_2_9") (pintype "power_in"))
      (node (ref "L9") (pin "1") (pinfunction "1_1") (pintype "passive"))
    )
    (net (code "15") (name "/BPF_OUT1") (class "Default")
      (node (ref "C96") (pin "1") (pinfunction "1_1") (pintype "passive"))
      (node (ref "D3") (pin "2") (pinfunction "A_2") (pintype "passive"))
      (node (ref "IC3") (pin "4") (pinfunction "DRAIN1_4") (pintype "passive"))
      (node (ref "K27") (pin "9") (pinfunction "COIL_2_9") (pintype "power_in"))
      (node (ref "L49") (pin "1") (pinfunction "1_1") (pintype "passive"))
    )
    (net (code "16") (name "/BPF_OUT2") (class "Default")
      (node (ref "C89") (pin "1") (pinfunction "1_1") (pintype "passive"))
      (node (ref "D4") (pin "2") (pinfunction "A_2") (pintype "passive"))
      (node (ref "IC3") (pin "5") (pinfunction "DRAIN2_5") (pintype "passive"))
      (node (ref "K25") (pin "9") (pinfunction "COIL_2_9") (pintype "power_in"))
      (node (ref "L45") (pin "1") (pinfunction "1_1") (pintype "passive"))
    )
    (net (code "17") (name "/BPF_OUT3") (class "Default")
      (node (ref "C79") (pin "1") (pinfunction "1_1") (pintype "passive"))
      (node (ref "D5") (pin "2") (pinfunction "A_2") (pintype "passive"))
      (node (ref "IC3") (pin "6") (pinfunction "DRAIN3_6") (pintype "passive"))
      (node (ref "K23") (pin "9") (pinfunction "COIL_2_9") (pintype "power_in"))
      (node (ref "L41") (pin "1") (pinfunction "1_1") (pintype "passive"))
    )
    (net (code "18") (name "/BPF_OUT4") (class "Default")
      (node (ref "C66") (pin "1") (pinfunction "1_1") (pintype "passive"))
      (node (ref "D9") (pin "2") (pinfunction "A_2") (pintype "passive"))
      (node (ref "IC3") (pin "11") (pinfunction "DRAIN4_11") (pintype "passive"))
      (node (ref "K21") (pin "9") (pinfunction "COIL_2_9") (pintype "power_in"))
      (node (ref "L37") (pin "1") (pinfunction "1_1") (pintype "passive"))
    )
    (net (code "19") (name "/BPF_OUT5") (class "Default")
      (node (ref "C58") (pin "1") (pinfunction "1_1") (pintype "passive"))
      (node (ref "D8") (pin "2") (pinfunction "A_2") (pintype "passive"))
      (node (ref "IC3") (pin "12") (pinfunction "DRAIN5_12") (pintype "passive"))
      (node (ref "K19") (pin "9") (pinfunction "COIL_2_9") (pintype "power_in"))
      (node (ref "L33") (pin "1") (pinfunction "1_1") (pintype "passive"))
    )
    (net (code "20") (name "/BPF_OUT6") (class "Default")
      (node (ref "C50") (pin "1") (pinfunction "1_1") (pintype "passive"))
      (node (ref "D7") (pin "2") (pinfunction "A_2") (pintype "passive"))
      (node (ref "IC3") (pin "13") (pinfunction "DRAIN6_13") (pintype "passive"))
      (node (ref "K17") (pin "9") (pinfunction "COIL_2_9") (pintype "power_in"))
      (node (ref "L29") (pin "1") (pinfunction "1_1") (pintype "passive"))
    )
    (net (code "21") (name "/BPF_OUT7") (class "Default")
      (node (ref "C41") (pin "1") (pinfunction "1_1") (pintype "passive"))
      (node (ref "D6") (pin "2") (pinfunction "A_2") (pintype "passive"))
      (node (ref "IC3") (pin "14") (pinfunction "DRAIN7_14") (pintype "passive"))
      (node (ref "K14") (pin "9") (pinfunction "COIL_2_9") (pintype "power_in"))
      (node (ref "L25") (pin "1") (pinfunction "1_1") (pintype "passive"))
    )
    (net (code "22") (name "/BPF_OUT8") (class "Default")
      (node (ref "C31") (pin "1") (pinfunction "1_1") (pintype "passive"))
      (node (ref "D10") (pin "2") (pinfunction "A_2") (pintype "passive"))
      (node (ref "IC4") (pin "3") (pinfunction "DRAIN0_3") (pintype "passive"))
      (node (ref "K10") (pin "9") (pinfunction "COIL_2_9") (pintype "power_in"))
      (node (ref "L20") (pin "1") (pinfunction "1_1") (pintype "passive"))
    )
    (net (code "23") (name "/BPF_OUT9") (class "Default")
      (node (ref "C24") (pin "1") (pinfunction "1_1") (pintype "passive"))
      (node (ref "D11") (pin "2") (pinfunction "A_2") (pintype "passive"))
      (node (ref "IC4") (pin "4") (pinfunction "DRAIN1_4") (pintype "passive"))
      (node (ref "K8") (pin "9") (pinfunction "COIL_2_9") (pintype "power_in"))
      (node (ref "L16") (pin "1") (pinfunction "1_1") (pintype "passive"))
    )
    (net (code "24") (name "/DAC") (class "Default")
      (node (ref "J1") (pin "5") (pinfunction "CON_5") (pintype "passive"))
      (node (ref "K13") (pin "10") (pinfunction "NO_10") (pintype "passive"))
    )
    (net (code "25") (name "/HPF_OUT") (class "Default")
      (node (ref "C16") (pin "1") (pinfunction "1_1") (pintype "passive"))
      (node (ref "D12") (pin "2") (pinfunction "A_2") (pintype "passive"))
      (node (ref "IC4") (pin "5") (pinfunction "DRAIN2_5") (pintype "passive"))
      (node (ref "K5") (pin "9") (pinfunction "COIL_2_9") (pintype "power_in"))
      (node (ref "L12") (pin "1") (pinfunction "1_1") (pintype "passive"))
    )
    (net (code "26") (name "/LNA_ON") (class "Default")
      (node (ref "C23") (pin "1") (pinfunction "1_1") (pintype "passive"))
      (node (ref "D15") (pin "2") (pinfunction "A_2") (pintype "passive"))
      (node (ref "IC4") (pin "12") (pinfunction "DRAIN5_12") (pintype "passive"))
      (node (ref "K7") (pin "1") (pinfunction "1_1") (pintype "passive"))
      (node (ref "Q1") (pin "1") (pinfunction "GATE_1") (pintype "passive"))
      (node (ref "R3") (pin "2") (pinfunction "2_2") (pintype "passive"))
    )
    (net (code "27") (name "/LPF_ON") (class "Default")
      (node (ref "C38") (pin "1") (pinfunction "1_1") (pintype "passive"))
      (node (ref "D16") (pin "2") (pinfunction "A_2") (pintype "passive"))
      (node (ref "IC4") (pin "11") (pinfunction "DRAIN4_11") (pintype "passive"))
      (node (ref "K12") (pin "1") (pinfunction "1_1") (pintype "passive"))
    )
    (net (code "28") (name "/RFUNT_ALC") (class "Default")
      (node (ref "J5") (pin "11") (pinfunction "11_11") (pintype "passive"))
      (node (ref "J6") (pin "11") (pinfunction "11_11") (pintype "passive"))
    )
    (net (code "29") (name "/RFUNT_CLK") (class "Default")
      (node (ref "IC3") (pin "15") (pinfunction "SRCK_15") (pintype "passive"))
      (node (ref "IC4") (pin "15") (pinfunction "SRCK_15") (pintype "passive"))
      (node (ref "IC5") (pin "15") (pinfunction "SRCK_15") (pintype "passive"))
      (node (ref "J5") (pin "5") (pinfunction "5_5") (pintype "passive"))
      (node (ref "J6") (pin "5") (pinfunction "5_5") (pintype "passive"))
    )
    (net (code "30") (name "/RFUNT_DATA_IN") (class "Default")
      (node (ref "IC3") (pin "2") (pinfunction "SER_IN_2") (pintype "passive"))
      (node (ref "J6") (pin "7") (pinfunction "7_7") (pintype "passive"))
    )
    (net (code "31") (name "/RFUNT_DATA_OUT") (class "Default")
      (node (ref "IC5") (pin "9") (pinfunction "SER_OUT_9") (pintype "passive"))
      (node (ref "J5") (pin "7") (pinfunction "7_7") (pintype "passive"))
    )
    (net (code "32") (name "/RFUNT_OE") (class "Default")
      (node (ref "IC3") (pin "8") (pinfunction "~{G}_8") (pintype "passive"))
      (node (ref "IC4") (pin "8") (pinfunction "~{G}_8") (pintype "passive"))
      (node (ref "IC5") (pin "8") (pinfunction "~{G}_8") (pintype "passive"))
      (node (ref "J5") (pin "8") (pinfunction "8_8") (pintype "passive"))
      (node (ref "J6") (pin "8") (pinfunction "8_8") (pintype "passive"))
      (node (ref "R2") (pin "1") (pinfunction "1_1") (pintype "passive"))
    )
    (net (code "33") (name "/RFUNT_RCLK") (class "Default")
      (node (ref "IC3") (pin "10") (pinfunction "RCK_10") (pintype "passive"))
      (node (ref "IC4") (pin "10") (pinfunction "RCK_10") (pintype "passive"))
      (node (ref "IC5") (pin "10") (pinfunction "RCK_10") (pintype "passive"))
      (node (ref "J5") (pin "6") (pinfunction "6_6") (pintype "passive"))
      (node (ref "J6") (pin "6") (pinfunction "6_6") (pintype "passive"))
    )
    (net (code "34") (name "/RFUNT_THERM") (class "Default")
      (node (ref "J5") (pin "12") (pinfunction "12_12") (pintype "passive"))
      (node (ref "J6") (pin "12") (pinfunction "12_12") (pintype "passive"))
    )
    (net (code "35") (name "/SWR_BACKW") (class "Default")
      (node (ref "J5") (pin "9") (pinfunction "9_9") (pintype "passive"))
      (node (ref "J6") (pin "9") (pinfunction "9_9") (pintype "passive"))
    )
    (net (code "36") (name "/SWR_FORW") (class "Default")
      (node (ref "J5") (pin "10") (pinfunction "10_10") (pintype "passive"))
      (node (ref "J6") (pin "10") (pinfunction "10_10") (pintype "passive"))
    )
    (net (code "37") (name "/TX") (class "Default")
      (node (ref "C40") (pin "1") (pinfunction "1_1") (pintype "passive"))
      (node (ref "D14") (pin "2") (pinfunction "A_2") (pintype "passive"))
      (node (ref "IC4") (pin "13") (pinfunction "DRAIN6_13") (pintype "passive"))
      (node (ref "K16") (pin "1") (pinfunction "1_1") (pintype "passive"))
      (node (ref "L23") (pin "1") (pinfunction "1_1") (pintype "passive"))
    )
    (net (code "38") (name "/WM8731_SCK") (class "Default")
      (node (ref "J5") (pin "3") (pinfunction "3_3") (pintype "passive"))
      (node (ref "J6") (pin "3") (pinfunction "3_3") (pintype "passive"))
    )
    (net (code "39") (name "/WM8731_SDA") (class "Default")
      (node (ref "J5") (pin "4") (pinfunction "4_4") (pintype "passive"))
      (node (ref "J6") (pin "4") (pinfunction "4_4") (pintype "passive"))
    )
    (net (code "40") (name "GND") (class "Default")
      (node (ref "C10") (pin "2") (pinfunction "2_2") (pintype "passive"))
      (node (ref "C100") (pin "2") (pinfunction "2_2") (pintype "passive"))
      (node (ref "C11") (pin "2") (pinfunction "2_2") (pintype "passive"))
      (node (ref "C12") (pin "2") (pinfunction "2_2") (pintype "passive"))
      (node (ref "C19") (pin "1") (pinfunction "1_1") (pintype "passive"))
      (node (ref "C20") (pin "1") (pinfunction "1_1") (pintype "passive"))
      (node (ref "C25") (pin "2") (pinfunction "2_2") (pintype "passive"))
      (node (ref "C26") (pin "2") (pinfunction "2_2") (pintype "passive"))
      (node (ref "C28") (pin "2") (pinfunction "2_2") (pintype "passive"))
      (node (ref "C32") (pin "2") (pinfunction "2_2") (pintype "passive"))
      (node (ref "C33") (pin "2") (pinfunction "2_2") (pintype "passive"))
      (node (ref "C35") (pin "2") (pinfunction "2_2") (pintype "passive"))
      (node (ref "C42") (pin "2") (pinfunction "2_2") (pintype "passive"))
      (node (ref "C43") (pin "2") (pinfunction "2_2") (pintype "passive"))
      (node (ref "C45") (pin "2") (pinfunction "2_2") (pintype "passive"))
      (node (ref "C46") (pin "2") (pinfunction "2_2") (pintype "passive"))
      (node (ref "C47") (pin "2") (pinfunction "2_2") (pintype "passive"))
      (node (ref "C51") (pin "2") (pinfunction "2_2") (pintype "passive"))
      (node (ref "C52") (pin "2") (pinfunction "2_2") (pintype "passive"))
      (node (ref "C54") (pin "2") (pinfunction "2_2") (pintype "passive"))
      (node (ref "C55") (pin "2") (pinfunction "2_2") (pintype "passive"))
      (node (ref "C59") (pin "2") (pinfunction "2_2") (pintype "passive"))
      (node (ref "C60") (pin "2") (pinfunction "2_2") (pintype "passive"))
      (node (ref "C62") (pin "2") (pinfunction "2_2") (pintype "passive"))
      (node (ref "C63") (pin "2") (pinfunction "2_2") (pintype "passive"))
      (node (ref "C67") (pin "2") (pinfunction "2_2") (pintype "passive"))
      (node (ref "C68") (pin "2") (pinfunction "2_2") (pintype "passive"))
      (node (ref "C70") (pin "2") (pinfunction "2_2") (pintype "passive"))
      (node (ref "C71") (pin "2") (pinfunction "-_2") (pintype "passive"))
      (node (ref "C72") (pin "1") (pinfunction "1_1") (pintype "passive"))
      (node (ref "C73") (pin "1") (pinfunction "1_1") (pintype "passive"))
      (node (ref "C74") (pin "1") (pinfunction "1_1") (pintype "passive"))
      (node (ref "C75") (pin "1") (pinfunction "1_1") (pintype "passive"))
      (node (ref "C78") (pin "2") (pinfunction "2_2") (pintype "passive"))
      (node (ref "C80") (pin "2") (pinfunction "2_2") (pintype "passive"))
      (node (ref "C81") (pin "2") (pinfunction "2_2") (pintype "passive"))
      (node (ref "C83") (pin "2") (pinfunction "2_2") (pintype "passive"))
      (node (ref "C84") (pin "1") (pinfunction "1_1") (pintype "passive"))
      (node (ref "C85") (pin "1") (pinfunction "1_1") (pintype "passive"))
      (node (ref "C86") (pin "1") (pinfunction "1_1") (pintype "passive"))
      (node (ref "C90") (pin "2") (pinfunction "2_2") (pintype "passive"))
      (node (ref "C91") (pin "2") (pinfunction "2_2") (pintype "passive"))
      (node (ref "C93") (pin "2") (pinfunction "2_2") (pintype "passive"))
      (node (ref "C97") (pin "2") (pinfunction "2_2") (pintype "passive"))
      (node (ref "C98") (pin "2") (pinfunction "2_2") (pintype "passive"))
      (node (ref "D1") (pin "1") (pinfunction "A_1") (pintype "passive"))
      (node (ref "D1") (pin "2") (pinfunction "C_2") (pintype "passive"))
      (node (ref "F1") (pin "1") (pinfunction "GND_1") (pintype "power_in"))
      (node (ref "F1") (pin "3") (pinfunction "GND_3") (pintype "power_in"))
      (node (ref "F1") (pin "4") (pinfunction "GND_4") (pintype "power_in"))
      (node (ref "F1") (pin "5") (pinfunction "GND_5") (pintype "power_in"))
      (node (ref "F1") (pin "7") (pinfunction "GND_7") (pintype "power_in"))
      (node (ref "F1") (pin "8") (pinfunction "GND_8") (pintype "power_in"))
      (node (ref "F2") (pin "1") (pinfunction "GND_1") (pintype "power_in"))
      (node (ref "F2") (pin "3") (pinfunction "GND_3") (pintype "power_in"))
      (node (ref "F2") (pin "4") (pinfunction "GND_4") (pintype "power_in"))
      (node (ref "F2") (pin "5") (pinfunction "GND_5") (pintype "power_in"))
      (node (ref "F2") (pin "7") (pinfunction "GND_7") (pintype "power_in"))
      (node (ref "F2") (pin "8") (pinfunction "GND_8") (pintype "power_in"))
      (node (ref "IC1") (pin "2") (pinfunction "GND_1_2") (pintype "passive"))
      (node (ref "IC1") (pin "4") (pinfunction "GND_2_4") (pintype "passive"))
      (node (ref "IC2") (pin "10") (pinfunction "GND_1_10") (pintype "passive"))
      (node (ref "IC2") (pin "11") (pinfunction "GND_2_11") (pintype "passive"))
      (node (ref "IC2") (pin "12") (pinfunction "VSS_EXT/GND_12") (pintype "passive"))
      (node (ref "IC2") (pin "13") (pinfunction "P/S_13") (pintype "passive"))
      (node (ref "IC2") (pin "18") (pinfunction "GND_3_18") (pintype "passive"))
      (node (ref "IC2") (pin "21") (pinfunction "EP_21") (pintype "passive"))
      (node (ref "IC2") (pin "3") (pinfunction "DATA_3") (pintype "passive"))
      (node (ref "IC2") (pin "4") (pinfunction "CLOCK_4") (pintype "passive"))
      (node (ref "IC2") (pin "7") (pinfunction "PUP1_7") (pintype "passive"))
      (node (ref "IC2") (pin "8") (pinfunction "PUP2_8") (pintype "passive"))
      (node (ref "IC3") (pin "16") (pinfunction "GND_16") (pintype "passive"))
      (node (ref "IC4") (pin "16") (pinfunction "GND_16") (pintype "passive"))
      (node (ref "IC5") (pin "16") (pinfunction "GND_16") (pintype "passive"))
      (node (ref "IC6") (pin "2") (pinfunction "GND_2") (pintype "passive"))
      (node (ref "J1") (pin "1") (pinfunction "GND_1") (pintype "passive"))
      (node (ref "J1") (pin "2") (pinfunction "GND_2") (pintype "passive"))
      (node (ref "J1") (pin "3") (pinfunction "GND_3") (pintype "passive"))
      (node (ref "J1") (pin "4") (pinfunction "GND_4") (pintype "passive"))
      (node (ref "J2") (pin "1") (pinfunction "GND_1") (pintype "passive"))
      (node (ref "J2") (pin "2") (pinfunction "GND_2") (pintype "passive"))
      (node (ref "J2") (pin "3") (pinfunction "GND_3") (pintype "passive"))
      (node (ref "J2") (pin "4") (pinfunction "GND_4") (pintype "passive"))
      (node (ref "J3") (pin "1") (pinfunction "GND_1") (pintype "passive"))
      (node (ref "J3") (pin "2") (pinfunction "GND_2") (pintype "passive"))
      (node (ref "J3") (pin "3") (pinfunction "GND_3") (pintype "passive"))
      (node (ref "J3") (pin "4") (pinfunction "GND_4") (pintype "passive"))
      (node (ref "J4") (pin "1") (pinfunction "1_1") (pintype "passive"))
      (node (ref "J4") (pin "2") (pinfunction "2_2") (pintype "passive"))
      (node (ref "J5") (pin "1") (pinfunction "1_1") (pintype "passive"))
      (node (ref "J5") (pin "2") (pinfunction "2_2") (pintype "passive"))
      (node (ref "J6") (pin "1") (pinfunction "1_1") (pintype "passive"))
      (node (ref "J6") (pin "2") (pinfunction "2_2") (pintype "passive"))
      (node (ref "K1") (pin "1") (pinfunction "NC_1") (pintype "passive"))
      (node (ref "K10") (pin "1") (pinfunction "NC_1") (pintype "passive"))
      (node (ref "K11") (pin "1") (pinfunction "NC_1") (pintype "passive"))
      (node (ref "K14") (pin "1") (pinfunction "NC_1") (pintype "passive"))
      (node (ref "K15") (pin "1") (pinfunction "NC_1") (pintype "passive"))
      (node (ref "K17") (pin "1") (pinfunction "NC_1") (pintype "passive"))
      (node (ref "K18") (pin "1") (pinfunction "NC_1") (pintype "passive"))
      (node (ref "K19") (pin "1") (pinfunction "NC_1") (pintype "passive"))
      (node (ref "K2") (pin "1") (pinfunction "NC_1") (pintype "passive"))
      (node (ref "K20") (pin "1") (pinfunction "NC_1") (pintype "passive"))
      (node (ref "K21") (pin "1") (pinfunction "NC_1") (pintype "passive"))
      (node (ref "K22") (pin "1") (pinfunction "NC_1") (pintype "passive"))
      (node (ref "K23") (pin "1") (pinfunction "NC_1") (pintype "passive"))
      (node (ref "K24") (pin "1") (pinfunction "NC_1") (pintype "passive"))
      (node (ref "K25") (pin "1") (pinfunction "NC_1") (pintype "passive"))
      (node (ref "K26") (pin "1") (pinfunction "NC_1") (pintype "passive"))
      (node (ref "K27") (pin "1") (pinfunction "NC_1") (pintype "passive"))
      (node (ref "K28") (pin "1") (pinfunction "NC_1") (pintype "passive"))
      (node (ref "K3") (pin "1") (pinfunction "NC_1") (pintype "passive"))
      (node (ref "K4") (pin "1") (pinfunction "NC_1") (pintype "passive"))
      (node (ref "K5") (pin "1") (pinfunction "NC_1") (pintype "passive"))
      (node (ref "K6") (pin "1") (pinfunction "NC_1") (pintype "passive"))
      (node (ref "K8") (pin "1") (pinfunction "NC_1") (pintype "passive"))
      (node (ref "K9") (pin "1") (pinfunction "NC_1") (pintype "passive"))
      (node (ref "L15") (pin "1") (pinfunction "1_1") (pintype "passive"))
      (node (ref "L19") (pin "1") (pinfunction "1_1") (pintype "passive"))
      (node (ref "L24") (pin "1") (pinfunction "1_1") (pintype "passive"))
      (node (ref "L28") (pin "1") (pinfunction "1_1") (pintype "passive"))
      (node (ref "L3") (pin "1") (pinfunction "1_1") (pintype "passive"))
      (node (ref "L32") (pin "1") (pinfunction "1_1") (pintype "passive"))
      (node (ref "L36") (pin "1") (pinfunction "1_1") (pintype "passive"))
      (node (ref "L4") (pin "1") (pinfunction "1_1") (pintype "passive"))
      (node (ref "L40") (pin "1") (pinfunction "1_1") (pintype "passive"))
      (node (ref "L44") (pin "1") (pinfunction "1_1") (pintype "passive"))
      (node (ref "L48") (pin "1") (pinfunction "1_1") (pintype "passive"))
      (node (ref "L5") (pin "1") (pinfunction "1_1") (pintype "passive"))
      (node (ref "L6") (pin "1") (pinfunction "1_1") (pintype "passive"))
      (node (ref "L7") (pin "1") (pinfunction "1_1") (pintype "passive"))
      (node (ref "L8") (pin "1") (pinfunction "1_1") (pintype "passive"))
      (node (ref "M1") (pin "1") (pintype "passive"))
      (node (ref "M2") (pin "1") (pintype "passive"))
      (node (ref "M3") (pin "1") (pintype "passive"))
      (node (ref "M4") (pin "1") (pintype "passive"))
      (node (ref "U1") (pin "3") (pinfunction "GND_3") (pintype "power_in"))
      (node (ref "U1") (pin "6") (pinfunction "GND_6") (pintype "power_in"))
    )
    (net (code "41") (name "Net-(C1-Pad1)") (class "Default")
      (node (ref "C1") (pin "1") (pinfunction "1_1") (pintype "passive"))
      (node (ref "C2") (pin "2") (pinfunction "2_2") (pintype "passive"))
      (node (ref "C6") (pin "2") (pinfunction "2_2") (pintype "passive"))
      (node (ref "L1") (pin "2") (pinfunction "2_2") (pintype "passive"))
      (node (ref "L2") (pin "1") (pinfunction "1_1") (pintype "passive"))
    )
    (net (code "42") (name "Net-(C5-Pad1)") (class "Default")
      (node (ref "C5") (pin "1") (pinfunction "1_1") (pintype "passive"))
      (node (ref "L3") (pin "2") (pinfunction "2_2") (pintype "passive"))
    )
    (net (code "43") (name "Net-(C6-Pad1)") (class "Default")
      (node (ref "C6") (pin "1") (pinfunction "1_1") (pintype "passive"))
      (node (ref "L4") (pin "2") (pinfunction "2_2") (pintype "passive"))
    )
    (net (code "44") (name "Net-(C7-Pad1)") (class "Default")
      (node (ref "C7") (pin "1") (pinfunction "1_1") (pintype "passive"))
      (node (ref "L5") (pin "2") (pinfunction "2_2") (pintype "passive"))
    )
    (net (code "45") (name "Net-(C10-Pad1)") (class "Default")
      (node (ref "C10") (pin "1") (pinfunction "1_1") (pintype "passive"))
      (node (ref "C2") (pin "1") (pinfunction "1_1") (pintype "passive"))
      (node (ref "C3") (pin "1") (pinfunction "1_1") (pintype "passive"))
      (node (ref "C7") (pin "2") (pinfunction "2_2") (pintype "passive"))
      (node (ref "L2") (pin "2") (pinfunction "2_2") (pintype "passive"))
      (node (ref "L6") (pin "2") (pinfunction "2_2") (pintype "passive"))
    )
    (net (code "46") (name "Net-(C11-Pad1)") (class "Default")
      (node (ref "C11") (pin "1") (pinfunction "1_1") (pintype "passive"))
      (node (ref "C3") (pin "2") (pinfunction "2_2") (pintype "passive"))
      (node (ref "C4") (pin "1") (pinfunction "1_1") (pintype "passive"))
      (node (ref "L7") (pin "2") (pinfunction "2_2") (pintype "passive"))
    )
    (net (code "47") (name "Net-(C15-Pad1)") (class "Default")
      (node (ref "C15") (pin "1") (pinfunction "1_1") (pintype "passive"))
      (node (ref "K7") (pin "4") (pinfunction "4_4") (pintype "passive"))
    )
    (net (code "48") (name "Net-(C18-Pad1)") (class "Default")
      (node (ref "C18") (pin "1") (pinfunction "1_1") (pintype "passive"))
      (node (ref "K7") (pin "5") (pinfunction "5_5") (pintype "passive"))
    )
    (net (code "49") (name "Net-(C21-Pad1)") (class "Default")
      (node (ref "C21") (pin "1") (pinfunction "1_1") (pintype "passive"))
      (node (ref "C25") (pin "1") (pinfunction "1_1") (pintype "passive"))
      (node (ref "L13") (pin "2") (pinfunction "2_2") (pintype "passive"))
    )
    (net (code "50") (name "Net-(C21-Pad2)") (class "Default")
      (node (ref "C21") (pin "2") (pinfunction "2_2") (pintype "passive"))
      (node (ref "C22") (pin "1") (pinfunction "1_1") (pintype "passive"))
      (node (ref "C28") (pin "1") (pinfunction "1_1") (pintype "passive"))
      (node (ref "L15") (pin "2") (pinfunction "2_2") (pintype "passive"))
    )
    (net (code "51") (name "Net-(C22-Pad2)") (class "Default")
      (node (ref "C22") (pin "2") (pinfunction "2_2") (pintype "passive"))
      (node (ref "C26") (pin "1") (pinfunction "1_1") (pintype "passive"))
      (node (ref "L14") (pin "1") (pinfunction "1_1") (pintype "passive"))
    )
    (net (code "52") (name "Net-(C29-Pad1)") (class "Default")
      (node (ref "C29") (pin "1") (pinfunction "1_1") (pintype "passive"))
      (node (ref "C32") (pin "1") (pinfunction "1_1") (pintype "passive"))
      (node (ref "L17") (pin "2") (pinfunction "2_2") (pintype "passive"))
    )
    (net (code "53") (name "Net-(C29-Pad2)") (class "Default")
      (node (ref "C29") (pin "2") (pinfunction "2_2") (pintype "passive"))
      (node (ref "C30") (pin "1") (pinfunction "1_1") (pintype "passive"))
      (node (ref "C35") (pin "1") (pinfunction "1_1") (pintype "passive"))
      (node (ref "L19") (pin "2") (pinfunction "2_2") (pintype "passive"))
    )
    (net (code "54") (name "Net-(C30-Pad2)") (class "Default")
      (node (ref "C30") (pin "2") (pinfunction "2_2") (pintype "passive"))
      (node (ref "C33") (pin "1") (pinfunction "1_1") (pintype "passive"))
      (node (ref "L18") (pin "1") (pinfunction "1_1") (pintype "passive"))
    )
    (net (code "55") (name "Net-(C36-Pad1)") (class "Default")
      (node (ref "C36") (pin "1") (pinfunction "1_1") (pintype "passive"))
      (node (ref "C42") (pin "1") (pinfunction "1_1") (pintype "passive"))
      (node (ref "L21") (pin "2") (pinfunction "2_2") (pintype "passive"))
    )
    (net (code "56") (name "Net-(C36-Pad2)") (class "Default")
      (node (ref "C36") (pin "2") (pinfunction "2_2") (pintype "passive"))
      (node (ref "C37") (pin "1") (pinfunction "1_1") (pintype "passive"))
      (node (ref "C46") (pin "1") (pinfunction "1_1") (pintype "passive"))
      (node (ref "L24") (pin "2") (pinfunction "2_2") (pintype "passive"))
    )
    (net (code "57") (name "Net-(C37-Pad2)") (class "Default")
      (node (ref "C37") (pin "2") (pinfunction "2_2") (pintype "passive"))
      (node (ref "C43") (pin "1") (pinfunction "1_1") (pintype "passive"))
      (node (ref "L22") (pin "1") (pinfunction "1_1") (pintype "passive"))
    )
    (net (code "58") (name "Net-(C48-Pad1)") (class "Default")
      (node (ref "C48") (pin "1") (pinfunction "1_1") (pintype "passive"))
      (node (ref "C51") (pin "1") (pinfunction "1_1") (pintype "passive"))
      (node (ref "L26") (pin "2") (pinfunction "2_2") (pintype "passive"))
    )
    (net (code "59") (name "Net-(C48-Pad2)") (class "Default")
      (node (ref "C48") (pin "2") (pinfunction "2_2") (pintype "passive"))
      (node (ref "C49") (pin "1") (pinfunction "1_1") (pintype "passive"))
      (node (ref "C54") (pin "1") (pinfunction "1_1") (pintype "passive"))
      (node (ref "L28") (pin "2") (pinfunction "2_2") (pintype "passive"))
    )
    (net (code "60") (name "Net-(C49-Pad2)") (class "Default")
      (node (ref "C49") (pin "2") (pinfunction "2_2") (pintype "passive"))
      (node (ref "C52") (pin "1") (pinfunction "1_1") (pintype "passive"))
      (node (ref "L27") (pin "1") (pinfunction "1_1") (pintype "passive"))
    )
    (net (code "61") (name "Net-(C56-Pad1)") (class "Default")
      (node (ref "C56") (pin "1") (pinfunction "1_1") (pintype "passive"))
      (node (ref "C59") (pin "1") (pinfunction "1_1") (pintype "passive"))
      (node (ref "L30") (pin "2") (pinfunction "2_2") (pintype "passive"))
    )
    (net (code "62") (name "Net-(C56-Pad2)") (class "Default")
      (node (ref "C56") (pin "2") (pinfunction "2_2") (pintype "passive"))
      (node (ref "C57") (pin "1") (pinfunction "1_1") (pintype "passive"))
      (node (ref "C62") (pin "1") (pinfunction "1_1") (pintype "passive"))
      (node (ref "L32") (pin "2") (pinfunction "2_2") (pintype "passive"))
    )
    (net (code "63") (name "Net-(C57-Pad2)") (class "Default")
      (node (ref "C57") (pin "2") (pinfunction "2_2") (pintype "passive"))
      (node (ref "C60") (pin "1") (pinfunction "1_1") (pintype "passive"))
      (node (ref "L31") (pin "1") (pinfunction "1_1") (pintype "passive"))
    )
    (net (code "64") (name "Net-(C64-Pad1)") (class "Default")
      (node (ref "C64") (pin "1") (pinfunction "1_1") (pintype "passive"))
      (node (ref "C67") (pin "1") (pinfunction "1_1") (pintype "passive"))
      (node (ref "L34") (pin "2") (pinfunction "2_2") (pintype "passive"))
    )
    (net (code "65") (name "Net-(C64-Pad2)") (class "Default")
      (node (ref "C64") (pin "2") (pinfunction "2_2") (pintype "passive"))
      (node (ref "C65") (pin "1") (pinfunction "1_1") (pintype "passive"))
      (node (ref "C70") (pin "1") (pinfunction "1_1") (pintype "passive"))
      (node (ref "L36") (pin "2") (pinfunction "2_2") (pintype "passive"))
    )
    (net (code "66") (name "Net-(C65-Pad2)") (class "Default")
      (node (ref "C65") (pin "2") (pinfunction "2_2") (pintype "passive"))
      (node (ref "C68") (pin "1") (pinfunction "1_1") (pintype "passive"))
      (node (ref "L35") (pin "1") (pinfunction "1_1") (pintype "passive"))
    )
    (net (code "67") (name "Net-(C76-Pad1)") (class "Default")
      (node (ref "C76") (pin "1") (pinfunction "1_1") (pintype "passive"))
      (node (ref "C80") (pin "1") (pinfunction "1_1") (pintype "passive"))
      (node (ref "L38") (pin "2") (pinfunction "2_2") (pintype "passive"))
    )
    (net (code "68") (name "Net-(C76-Pad2)") (class "Default")
      (node (ref "C76") (pin "2") (pinfunction "2_2") (pintype "passive"))
      (node (ref "C77") (pin "1") (pinfunction "1_1") (pintype "passive"))
      (node (ref "C83") (pin "1") (pinfunction "1_1") (pintype "passive"))
      (node (ref "L40") (pin "2") (pinfunction "2_2") (pintype "passive"))
    )
    (net (code "69") (name "Net-(C77-Pad2)") (class "Default")
      (node (ref "C77") (pin "2") (pinfunction "2_2") (pintype "passive"))
      (node (ref "C81") (pin "1") (pinfunction "1_1") (pintype "passive"))
      (node (ref "L39") (pin "1") (pinfunction "1_1") (pintype "passive"))
    )
    (net (code "70") (name "Net-(C87-Pad1)") (class "Default")
      (node (ref "C87") (pin "1") (pinfunction "1_1") (pintype "passive"))
      (node (ref "C90") (pin "1") (pinfunction "1_1") (pintype "passive"))
      (node (ref "L42") (pin "2") (pinfunction "2_2") (pintype "passive"))
    )
    (net (code "71") (name "Net-(C87-Pad2)") (class "Default")
      (node (ref "C87") (pin "2") (pinfunction "2_2") (pintype "passive"))
      (node (ref "C88") (pin "1") (pinfunction "1_1") (pintype "passive"))
      (node (ref "C93") (pin "1") (pinfunction "1_1") (pintype "passive"))
      (node (ref "L44") (pin "2") (pinfunction "2_2") (pintype "passive"))
    )
    (net (code "72") (name "Net-(C88-Pad2)") (class "Default")
      (node (ref "C88") (pin "2") (pinfunction "2_2") (pintype "passive"))
      (node (ref "C91") (pin "1") (pinfunction "1_1") (pintype "passive"))
      (node (ref "L43") (pin "1") (pinfunction "1_1") (pintype "passive"))
    )
    (net (code "73") (name "Net-(C94-Pad1)") (class "Default")
      (node (ref "C94") (pin "1") (pinfunction "1_1") (pintype "passive"))
      (node (ref "C97") (pin "1") (pinfunction "1_1") (pintype "passive"))
      (node (ref "L46") (pin "2") (pinfunction "2_2") (pintype "passive"))
    )
    (net (code "74") (name "Net-(C95-Pad2)") (class "Default")
      (node (ref "C95") (pin "2") (pinfunction "2_2") (pintype "passive"))
      (node (ref "C98") (pin "1") (pinfunction "1_1") (pintype "passive"))
      (node (ref "L47") (pin "1") (pinfunction "1_1") (pintype "passive"))
    )
    (net (code "75") (name "Net-(C100-Pad1)") (class "Default")
      (node (ref "C100") (pin "1") (pinfunction "1_1") (pintype "passive"))
      (node (ref "C94") (pin "2") (pinfunction "2_2") (pintype "passive"))
      (node (ref "C95") (pin "1") (pinfunction "1_1") (pintype "passive"))
      (node (ref "L48") (pin "2") (pinfunction "2_2") (pintype "passive"))
    )
    (net (code "76") (name "Net-(D1-CATHODE{slash}ANODE)") (class "Default")
      (node (ref "D1") (pin "3") (pinfunction "CATHODE/ANODE_3") (pintype "passive"))
      (node (ref "K16") (pin "2") (pinfunction "2_2") (pintype "passive"))
      (node (ref "K7") (pin "3") (pinfunction "3_3") (pintype "passive"))
    )
    (net (code "77") (name "Net-(F1-IN{slash}OUT)") (class "Default")
      (node (ref "F1") (pin "2") (pinfunction "IN/OUT_2") (pintype "bidirectional"))
      (node (ref "K5") (pin "5") (pinfunction "COM_1_5") (pintype "passive"))
      (node (ref "K5") (pin "6") (pinfunction "COM_2_6") (pintype "passive"))
    )
    (net (code "78") (name "Net-(F1-OUT{slash}IN)") (class "Default")
      (node (ref "F1") (pin "6") (pinfunction "OUT/IN_6") (pintype "bidirectional"))
      (node (ref "K6") (pin "5") (pinfunction "COM_1_5") (pintype "passive"))
      (node (ref "K6") (pin "6") (pinfunction "COM_2_6") (pintype "passive"))
    )
    (net (code "79") (name "Net-(F2-IN{slash}OUT)") (class "Default")
      (node (ref "F2") (pin "2") (pinfunction "IN/OUT_2") (pintype "bidirectional"))
      (node (ref "K12") (pin "5") (pinfunction "5_5") (pintype "passive"))
    )
    (net (code "80") (name "Net-(F2-OUT{slash}IN)") (class "Default")
      (node (ref "F2") (pin "6") (pinfunction "OUT/IN_6") (pintype "bidirectional"))
      (node (ref "K12") (pin "4") (pinfunction "4_4") (pintype "passive"))
    )
    (net (code "81") (name "Net-(IC1-RF_IN)") (class "Default")
      (node (ref "C15") (pin "2") (pinfunction "2_2") (pintype "passive"))
      (node (ref "IC1") (pin "1") (pinfunction "RF_IN_1") (pintype "passive"))
    )
    (net (code "82") (name "Net-(IC1-RF_OUT{slash}DC_BIAS)") (class "Default")
      (node (ref "C18") (pin "2") (pinfunction "2_2") (pintype "passive"))
      (node (ref "IC1") (pin "3") (pinfunction "RF_OUT/DC_BIAS_3") (pintype "passive"))
      (node (ref "L11") (pin "1") (pinfunction "1_1") (pintype "passive"))
    )
    (net (code "83") (name "Net-(IC2-RF1)") (class "Default")
      (node (ref "IC2") (pin "2") (pinfunction "RF1_2") (pintype "passive"))
      (node (ref "K12") (pin "3") (pinfunction "3_3") (pintype "passive"))
    )
    (net (code "84") (name "Net-(IC2-RF2)") (class "Default")
      (node (ref "IC2") (pin "14") (pinfunction "RF2_14") (pintype "passive"))
      (node (ref "K7") (pin "6") (pinfunction "6_6") (pintype "passive"))
    )
    (net (code "85") (name "Net-(IC3-SER_OUT)") (class "Default")
      (node (ref "IC3") (pin "9") (pinfunction "SER_OUT_9") (pintype "passive"))
      (node (ref "IC4") (pin "2") (pinfunction "SER_IN_2") (pintype "passive"))
    )
    (net (code "86") (name "Net-(IC4-SER_OUT)") (class "Default")
      (node (ref "IC4") (pin "9") (pinfunction "SER_OUT_9") (pintype "passive"))
      (node (ref "IC5") (pin "2") (pinfunction "SER_IN_2") (pintype "passive"))
    )
    (net (code "87") (name "Net-(J3-CON)") (class "Default")
      (node (ref "J3") (pin "5") (pinfunction "CON_5") (pintype "passive"))
      (node (ref "K16") (pin "3") (pinfunction "3_3") (pintype "passive"))
    )
    (net (code "88") (name "Net-(K1-COM_1)") (class "Default")
      (node (ref "C1") (pin "2") (pinfunction "2_2") (pintype "passive"))
      (node (ref "C5") (pin "2") (pinfunction "2_2") (pintype "passive"))
      (node (ref "K1") (pin "5") (pinfunction "COM_1_5") (pintype "passive"))
      (node (ref "K1") (pin "6") (pinfunction "COM_2_6") (pintype "passive"))
      (node (ref "L1") (pin "1") (pinfunction "1_1") (pintype "passive"))
    )
    (net (code "89") (name "Net-(K2-COIL_1)") (class "Default")
      (node (ref "C9") (pin "1") (pinfunction "1_1") (pintype "passive"))
      (node (ref "K2") (pin "2") (pinfunction "COIL_1_2") (pintype "input"))
      (node (ref "L9") (pin "2") (pinfunction "2_2") (pintype "passive"))
    )
    (net (code "90") (name "Net-(K2-COM_1)") (class "Default")
      (node (ref "C12") (pin "1") (pinfunction "1_1") (pintype "passive"))
      (node (ref "C4") (pin "2") (pinfunction "2_2") (pintype "passive"))
      (node (ref "K2") (pin "5") (pinfunction "COM_1_5") (pintype "passive"))
      (node (ref "K2") (pin "6") (pinfunction "COM_2_6") (pintype "passive"))
      (node (ref "L8") (pin "2") (pinfunction "2_2") (pintype "passive"))
    )
    (net (code "91") (name "Net-(K3-COM_1)") (class "Default")
      (node (ref "K3") (pin "5") (pinfunction "COM_1_5") (pintype "passive"))
      (node (ref "K4") (pin "6") (pinfunction "COM_2_6") (pintype "passive"))
    )
    (net (code "92") (name "Net-(K4-COIL_1)") (class "Default")
      (node (ref "C14") (pin "1") (pinfunction "1_1") (pintype "passive"))
      (node (ref "K4") (pin "2") (pinfunction "COIL_1_2") (pintype "input"))
      (node (ref "L10") (pin "2") (pinfunction "2_2") (pintype "passive"))
    )
    (net (code "93") (name "Net-(K6-COIL_1)") (class "Default")
      (node (ref "C17") (pin "1") (pinfunction "1_1") (pintype "passive"))
      (node (ref "K6") (pin "2") (pinfunction "COIL_1_2") (pintype "input"))
      (node (ref "L12") (pin "2") (pinfunction "2_2") (pintype "passive"))
    )
    (net (code "94") (name "Net-(K7-Pad2)") (class "Default")
      (node (ref "K7") (pin "2") (pinfunction "2_2") (pintype "passive"))
      (node (ref "K7") (pin "7") (pinfunction "7_7") (pintype "passive"))
    )
    (net (code "95") (name "Net-(K8-COM_1)") (class "Default")
      (node (ref "K8") (pin "5") (pinfunction "COM_1_5") (pintype "passive"))
      (node (ref "L13") (pin "1") (pinfunction "1_1") (pintype "passive"))
    )
    (net (code "96") (name "Net-(K9-COIL_1)") (class "Default")
      (node (ref "C27") (pin "1") (pinfunction "1_1") (pintype "passive"))
      (node (ref "K9") (pin "2") (pinfunction "COIL_1_2") (pintype "input"))
      (node (ref "L16") (pin "2") (pinfunction "2_2") (pintype "passive"))
    )
    (net (code "97") (name "Net-(K9-COM_1)") (class "Default")
      (node (ref "K9") (pin "5") (pinfunction "COM_1_5") (pintype "passive"))
      (node (ref "L14") (pin "2") (pinfunction "2_2") (pintype "passive"))
    )
    (net (code "98") (name "Net-(K10-COM_1)") (class "Default")
      (node (ref "K10") (pin "5") (pinfunction "COM_1_5") (pintype "passive"))
      (node (ref "L17") (pin "1") (pinfunction "1_1") (pintype "passive"))
    )
    (net (code "99") (name "Net-(K11-COIL_1)") (class "Default")
      (node (ref "C34") (pin "1") (pinfunction "1_1") (pintype "passive"))
      (node (ref "K11") (pin "2") (pinfunction "COIL_1_2") (pintype "input"))
      (node (ref "L20") (pin "2") (pinfunction "2_2") (pintype "passive"))
    )
    (net (code "100") (name "Net-(K11-COM_1)") (class "Default")
      (node (ref "K11") (pin "5") (pinfunction "COM_1_5") (pintype "passive"))
      (node (ref "L18") (pin "2") (pinfunction "2_2") (pintype "passive"))
    )
    (net (code "101") (name "Net-(K12-Pad2)") (class "Default")
      (node (ref "K12") (pin "2") (pinfunction "2_2") (pintype "passive"))
      (node (ref "K12") (pin "7") (pinfunction "7_7") (pintype "passive"))
    )
    (net (code "102") (name "Net-(K12-Pad6)") (class "Default")
      (node (ref "K12") (pin "6") (pinfunction "6_6") (pintype "passive"))
      (node (ref "K16") (pin "7") (pinfunction "7_7") (pintype "passive"))
    )
    (net (code "103") (name "Net-(K13-COIL_2)") (class "Default")
      (node (ref "C39") (pin "1") (pinfunction "1_1") (pintype "passive"))
      (node (ref "K13") (pin "9") (pinfunction "COIL_2_9") (pintype "power_in"))
      (node (ref "L23") (pin "2") (pinfunction "2_2") (pintype "passive"))
    )
    (net (code "104") (name "Net-(K14-COM_1)") (class "Default")
      (node (ref "K14") (pin "5") (pinfunction "COM_1_5") (pintype "passive"))
      (node (ref "L21") (pin "1") (pinfunction "1_1") (pintype "passive"))
    )
    (net (code "105") (name "Net-(K15-COIL_1)") (class "Default")
      (node (ref "C44") (pin "1") (pinfunction "1_1") (pintype "passive"))
      (node (ref "K15") (pin "2") (pinfunction "COIL_1_2") (pintype "input"))
      (node (ref "L25") (pin "2") (pinfunction "2_2") (pintype "passive"))
    )
    (net (code "106") (name "Net-(K15-COM_1)") (class "Default")
      (node (ref "K15") (pin "5") (pinfunction "COM_1_5") (pintype "passive"))
      (node (ref "L22") (pin "2") (pinfunction "2_2") (pintype "passive"))
    )
    (net (code "107") (name "Net-(K16-Pad4)") (class "Default")
      (node (ref "K16") (pin "4") (pinfunction "4_4") (pintype "passive"))
      (node (ref "K16") (pin "5") (pinfunction "5_5") (pintype "passive"))
    )
    (net (code "108") (name "Net-(K17-COM_1)") (class "Default")
      (node (ref "K17") (pin "5") (pinfunction "COM_1_5") (pintype "passive"))
      (node (ref "L26") (pin "1") (pinfunction "1_1") (pintype "passive"))
    )
    (net (code "109") (name "Net-(K18-COIL_1)") (class "Default")
      (node (ref "C53") (pin "1") (pinfunction "1_1") (pintype "passive"))
      (node (ref "K18") (pin "2") (pinfunction "COIL_1_2") (pintype "input"))
      (node (ref "L29") (pin "2") (pinfunction "2_2") (pintype "passive"))
    )
    (net (code "110") (name "Net-(K18-COM_1)") (class "Default")
      (node (ref "K18") (pin "5") (pinfunction "COM_1_5") (pintype "passive"))
      (node (ref "L27") (pin "2") (pinfunction "2_2") (pintype "passive"))
    )
    (net (code "111") (name "Net-(K19-COM_1)") (class "Default")
      (node (ref "K19") (pin "5") (pinfunction "COM_1_5") (pintype "passive"))
      (node (ref "L30") (pin "1") (pinfunction "1_1") (pintype "passive"))
    )
    (net (code "112") (name "Net-(K20-COIL_1)") (class "Default")
      (node (ref "C61") (pin "1") (pinfunction "1_1") (pintype "passive"))
      (node (ref "K20") (pin "2") (pinfunction "COIL_1_2") (pintype "input"))
      (node (ref "L33") (pin "2") (pinfunction "2_2") (pintype "passive"))
    )
    (net (code "113") (name "Net-(K20-COM_1)") (class "Default")
      (node (ref "K20") (pin "5") (pinfunction "COM_1_5") (pintype "passive"))
      (node (ref "L31") (pin "2") (pinfunction "2_2") (pintype "passive"))
    )
    (net (code "114") (name "Net-(K21-COM_1)") (class "Default")
      (node (ref "K21") (pin "5") (pinfunction "COM_1_5") (pintype "passive"))
      (node (ref "L34") (pin "1") (pinfunction "1_1") (pintype "passive"))
    )
    (net (code "115") (name "Net-(K22-COIL_1)") (class "Default")
      (node (ref "C69") (pin "1") (pinfunction "1_1") (pintype "passive"))
      (node (ref "K22") (pin "2") (pinfunction "COIL_1_2") (pintype "input"))
      (node (ref "L37") (pin "2") (pinfunction "2_2") (pintype "passive"))
    )
    (net (code "116") (name "Net-(K22-COM_1)") (class "Default")
      (node (ref "K22") (pin "5") (pinfunction "COM_1_5") (pintype "passive"))
      (node (ref "L35") (pin "2") (pinfunction "2_2") (pintype "passive"))
    )
    (net (code "117") (name "Net-(K23-COM_1)") (class "Default")
      (node (ref "K23") (pin "5") (pinfunction "COM_1_5") (pintype "passive"))
      (node (ref "L38") (pin "1") (pinfunction "1_1") (pintype "passive"))
    )
    (net (code "118") (name "Net-(K24-COIL_1)") (class "Default")
      (node (ref "C82") (pin "1") (pinfunction "1_1") (pintype "passive"))
      (node (ref "K24") (pin "2") (pinfunction "COIL_1_2") (pintype "input"))
      (node (ref "L41") (pin "2") (pinfunction "2_2") (pintype "passive"))
    )
    (net (code "119") (name "Net-(K24-COM_1)") (class "Default")
      (node (ref "K24") (pin "5") (pinfunction "COM_1_5") (pintype "passive"))
      (node (ref "L39") (pin "2") (pinfunction "2_2") (pintype "passive"))
    )
    (net (code "120") (name "Net-(K25-COM_1)") (class "Default")
      (node (ref "K25") (pin "5") (pinfunction "COM_1_5") (pintype "passive"))
      (node (ref "L42") (pin "1") (pinfunction "1_1") (pintype "passive"))
    )
    (net (code "121") (name "Net-(K26-COIL_1)") (class "Default")
      (node (ref "C92") (pin "1") (pinfunction "1_1") (pintype "passive"))
      (node (ref "K26") (pin "2") (pinfunction "COIL_1_2") (pintype "input"))
      (node (ref "L45") (pin "2") (pinfunction "2_2") (pintype "passive"))
    )
    (net (code "122") (name "Net-(K26-COM_1)") (class "Default")
      (node (ref "K26") (pin "5") (pinfunction "COM_1_5") (pintype "passive"))
      (node (ref "L43") (pin "2") (pinfunction "2_2") (pintype "passive"))
    )
    (net (code "123") (name "Net-(K27-COM_1)") (class "Default")
      (node (ref "K27") (pin "5") (pinfunction "COM_1_5") (pintype "passive"))
      (node (ref "L46") (pin "1") (pinfunction "1_1") (pintype "passive"))
    )
    (net (code "124") (name "Net-(K28-COIL_1)") (class "Default")
      (node (ref "C99") (pin "1") (pinfunction "1_1") (pintype "passive"))
      (node (ref "K28") (pin "2") (pinfunction "COIL_1_2") (pintype "input"))
      (node (ref "L49") (pin "2") (pinfunction "2_2") (pintype "passive"))
    )
    (net (code "125") (name "Net-(K28-COM_1)") (class "Default")
      (node (ref "K28") (pin "5") (pinfunction "COM_1_5") (pintype "passive"))
      (node (ref "L47") (pin "2") (pinfunction "2_2") (pintype "passive"))
    )
    (net (code "126") (name "Net-(L11-Pad2)") (class "Default")
      (node (ref "L11") (pin "2") (pinfunction "2_2") (pintype "passive"))
      (node (ref "R1") (pin "1") (pinfunction "1_1") (pintype "passive"))
    )
    (net (code "127") (name "Net-(Q1-DRAIN)") (class "Default")
      (node (ref "C72") (pin "2") (pinfunction "2_2") (pintype "passive"))
      (node (ref "Q1") (pin "3") (pinfunction "DRAIN_3") (pintype "passive"))
      (node (ref "U1") (pin "1") (pinfunction "EN_1") (pintype "input"))
      (node (ref "U1") (pin "2") (pinfunction "IN_2") (pintype "power_in"))
    )
    (net (code "128") (name "Net-(U1-NR)") (class "Default")
      (node (ref "C73") (pin "2") (pinfunction "2_2") (pintype "passive"))
      (node (ref "U1") (pin "5") (pinfunction "NR_5") (pintype "passive"))
    )
    (net (code "129") (name "unconnected-(IC4-DRAIN7-Pad14)") (class "Default")
      (node (ref "IC4") (pin "14") (pinfunction "DRAIN7_14") (pintype "passive+no_connect"))
    )
    (net (code "130") (name "unconnected-(IC5-DRAIN6-Pad13)") (class "Default")
      (node (ref "IC5") (pin "13") (pinfunction "DRAIN6_13") (pintype "passive+no_connect"))
    )
    (net (code "131") (name "unconnected-(IC5-DRAIN7-Pad14)") (class "Default")
      (node (ref "IC5") (pin "14") (pinfunction "DRAIN7_14") (pintype "passive+no_connect"))
    )
    (net (code "132") (name "unconnected-(IC6-NC-Pad4)") (class "Default")
      (node (ref "IC6") (pin "4") (pinfunction "NC_4") (pintype "passive+no_connect"))
    )
    (net (code "133") (name "unconnected-(K3-COM_2-Pad6)") (class "Default")
      (node (ref "K3") (pin "6") (pinfunction "COM_2_6") (pintype "passive+no_connect"))
    )
    (net (code "134") (name "unconnected-(K4-COM_1-Pad5)") (class "Default")
      (node (ref "K4") (pin "5") (pinfunction "COM_1_5") (pintype "passive+no_connect"))
    )
    (net (code "135") (name "unconnected-(K8-COM_2-Pad6)") (class "Default")
      (node (ref "K8") (pin "6") (pinfunction "COM_2_6") (pintype "passive+no_connect"))
    )
    (net (code "136") (name "unconnected-(K9-COM_2-Pad6)") (class "Default")
      (node (ref "K9") (pin "6") (pinfunction "COM_2_6") (pintype "passive+no_connect"))
    )
    (net (code "137") (name "unconnected-(K10-COM_2-Pad6)") (class "Default")
      (node (ref "K10") (pin "6") (pinfunction "COM_2_6") (pintype "passive+no_connect"))
    )
    (net (code "138") (name "unconnected-(K11-COM_2-Pad6)") (class "Default")
      (node (ref "K11") (pin "6") (pinfunction "COM_2_6") (pintype "passive+no_connect"))
    )
    (net (code "139") (name "unconnected-(K13-COM_1-Pad5)") (class "Default")
      (node (ref "K13") (pin "5") (pinfunction "COM_1_5") (pintype "passive+no_connect"))
    )
    (net (code "140") (name "unconnected-(K14-COM_2-Pad6)") (class "Default")
      (node (ref "K14") (pin "6") (pinfunction "COM_2_6") (pintype "passive+no_connect"))
    )
    (net (code "141") (name "unconnected-(K15-COM_2-Pad6)") (class "Default")
      (node (ref "K15") (pin "6") (pinfunction "COM_2_6") (pintype "passive+no_connect"))
    )
    (net (code "142") (name "unconnected-(K17-COM_2-Pad6)") (class "Default")
      (node (ref "K17") (pin "6") (pinfunction "COM_2_6") (pintype "passive+no_connect"))
    )
    (net (code "143") (name "unconnected-(K18-COM_2-Pad6)") (class "Default")
      (node (ref "K18") (pin "6") (pinfunction "COM_2_6") (pintype "passive+no_connect"))
    )
    (net (code "144") (name "unconnected-(K19-COM_2-Pad6)") (class "Default")
      (node (ref "K19") (pin "6") (pinfunction "COM_2_6") (pintype "passive+no_connect"))
    )
    (net (code "145") (name "unconnected-(K20-COM_2-Pad6)") (class "Default")
      (node (ref "K20") (pin "6") (pinfunction "COM_2_6") (pintype "passive+no_connect"))
    )
    (net (code "146") (name "unconnected-(K21-COM_2-Pad6)") (class "Default")
      (node (ref "K21") (pin "6") (pinfunction "COM_2_6") (pintype "passive+no_connect"))
    )
    (net (code "147") (name "unconnected-(K22-COM_2-Pad6)") (class "Default")
      (node (ref "K22") (pin "6") (pinfunction "COM_2_6") (pintype "passive+no_connect"))
    )
    (net (code "148") (name "unconnected-(K23-COM_2-Pad6)") (class "Default")
      (node (ref "K23") (pin "6") (pinfunction "COM_2_6") (pintype "passive+no_connect"))
    )
    (net (code "149") (name "unconnected-(K24-COM_2-Pad6)") (class "Default")
      (node (ref "K24") (pin "6") (pinfunction "COM_2_6") (pintype "passive+no_connect"))
    )
    (net (code "150") (name "unconnected-(K25-COM_2-Pad6)") (class "Default")
      (node (ref "K25") (pin "6") (pinfunction "COM_2_6") (pintype "passive+no_connect"))
    )
    (net (code "151") (name "unconnected-(K26-COM_2-Pad6)") (class "Default")
      (node (ref "K26") (pin "6") (pinfunction "COM_2_6") (pintype "passive+no_connect"))
    )
    (net (code "152") (name "unconnected-(K27-COM_2-Pad6)") (class "Default")
      (node (ref "K27") (pin "6") (pinfunction "COM_2_6") (pintype "passive+no_connect"))
    )
    (net (code "153") (name "unconnected-(K28-COM_2-Pad6)") (class "Default")
      (node (ref "K28") (pin "6") (pinfunction "COM_2_6") (pintype "passive+no_connect"))
    )
  )
)
